# io-board-b-i.net
KiCad netlist of a schematic drawn in EAGLE
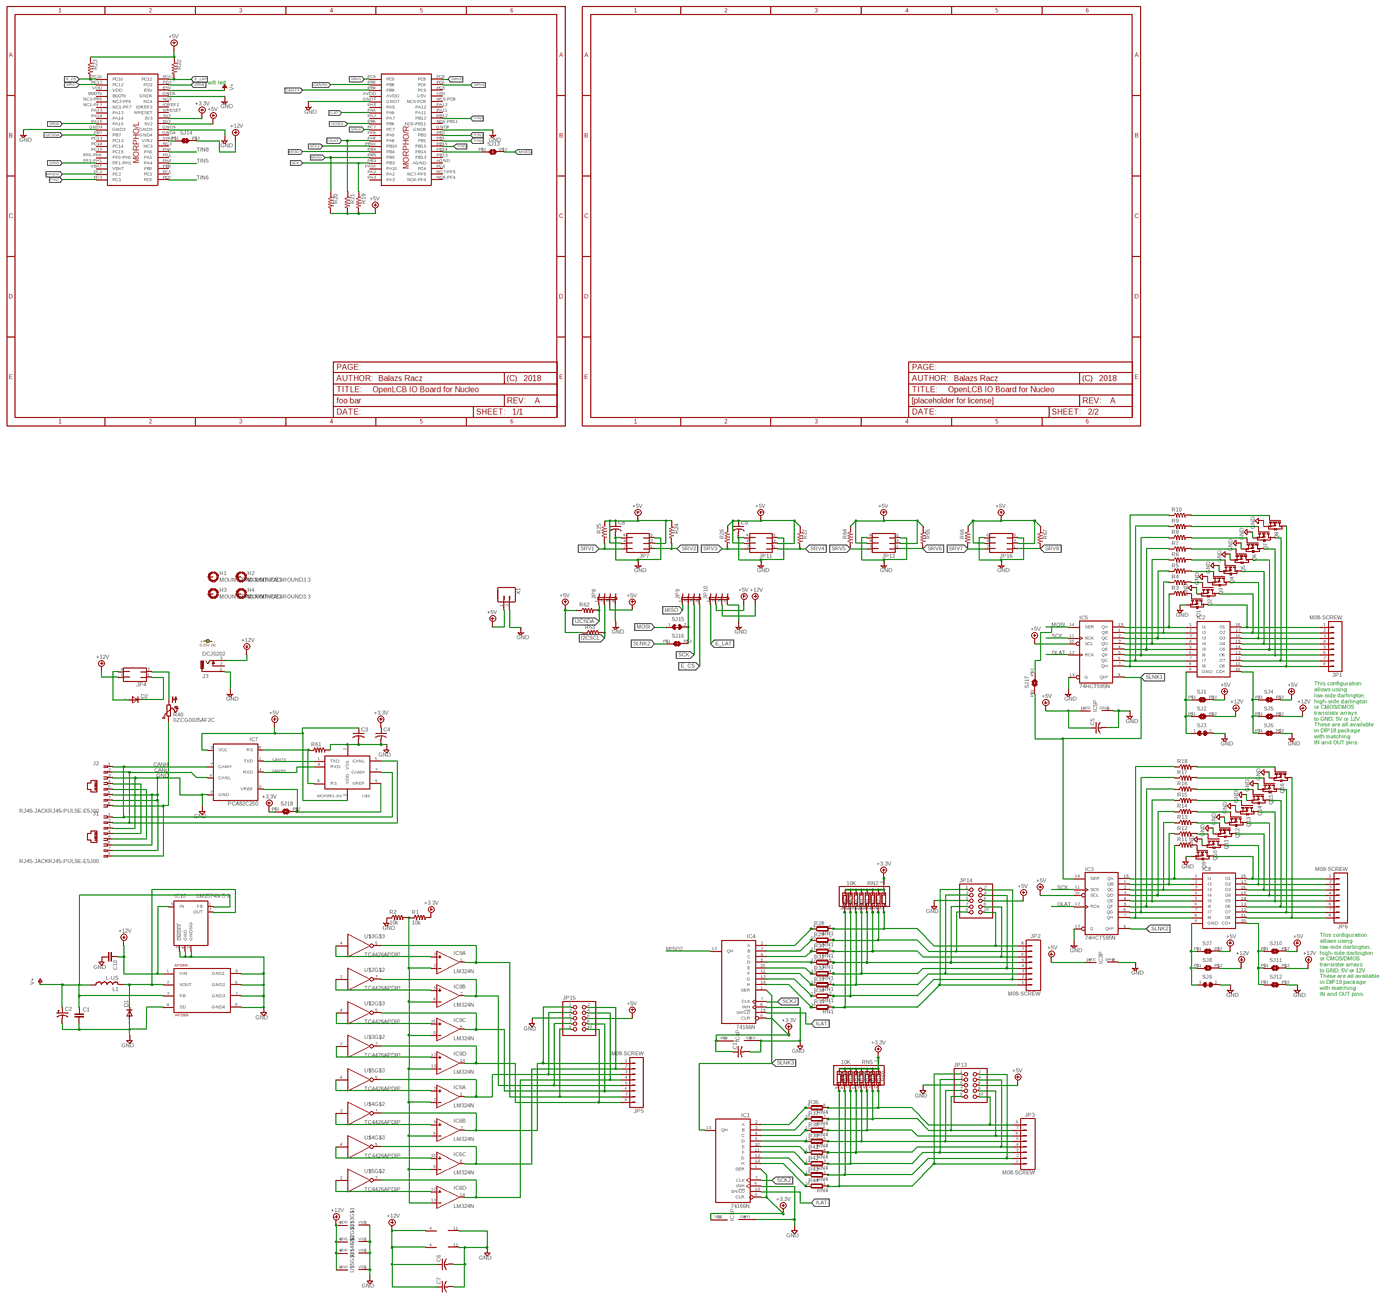
[diagram p0: schematic, sheet 1, overview]
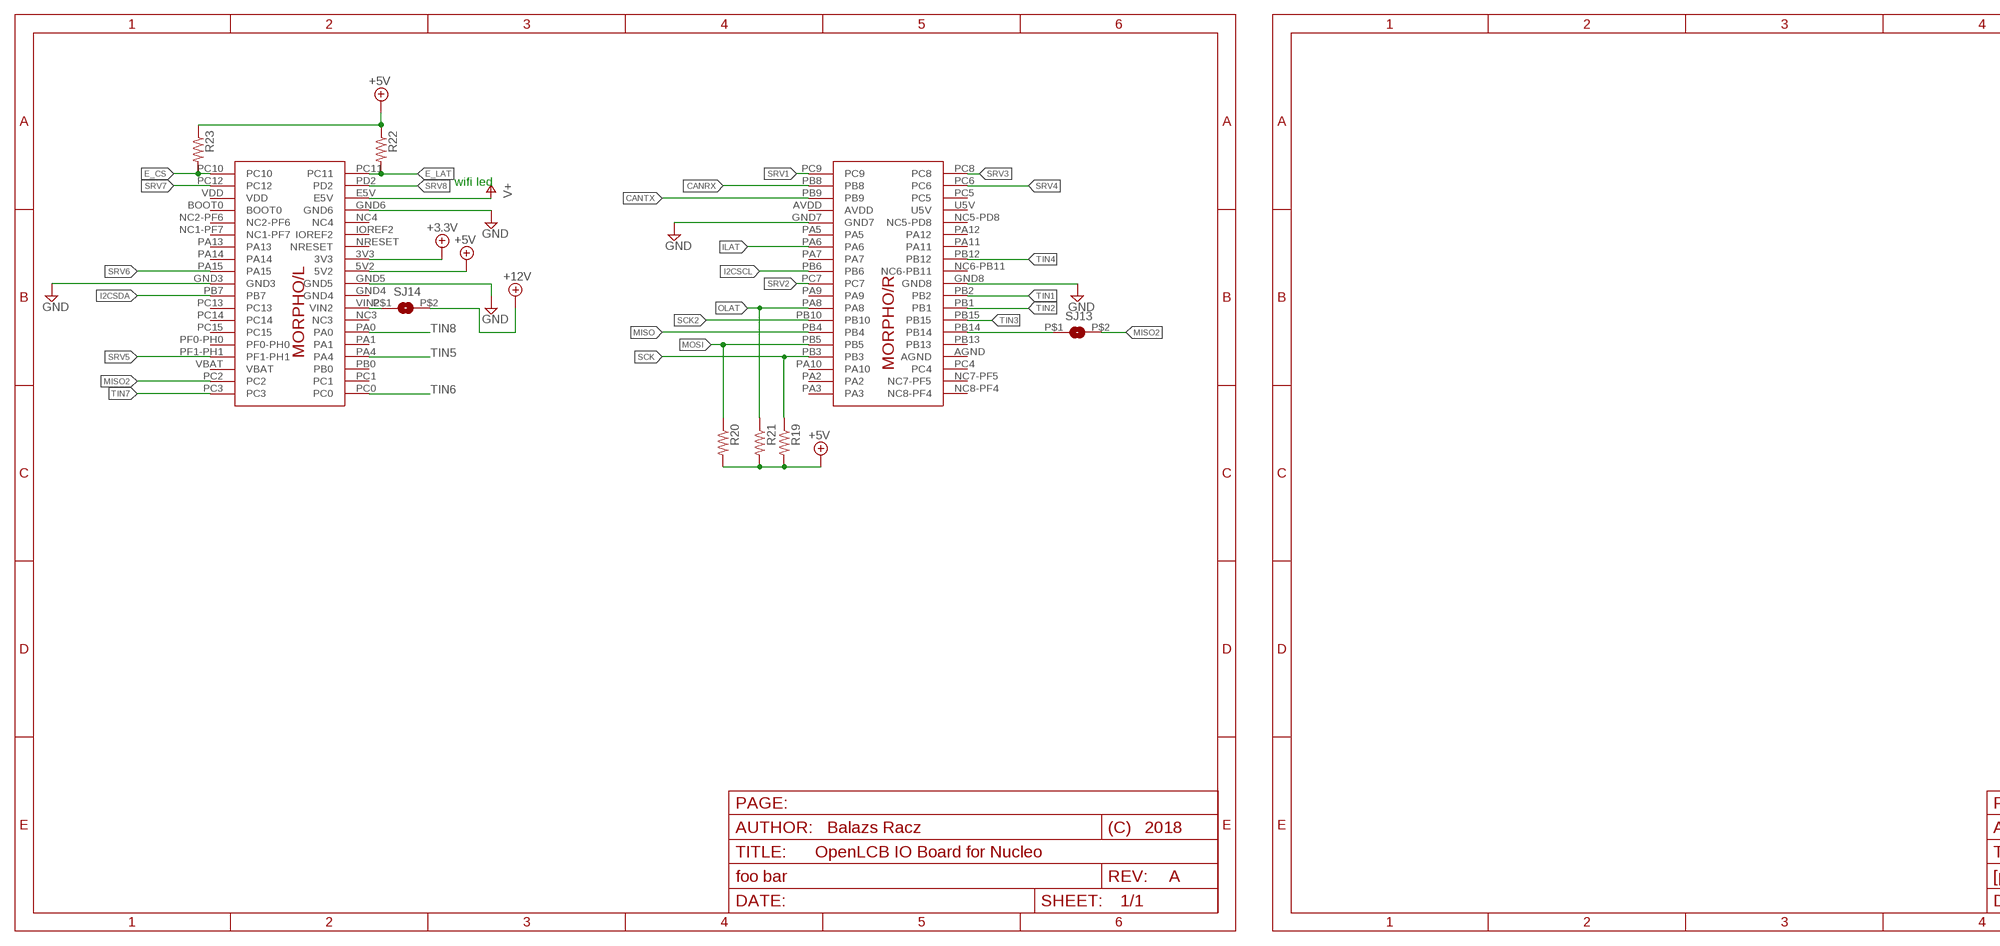
[diagram p1: schematic, sheet 1, part 1 of 4]
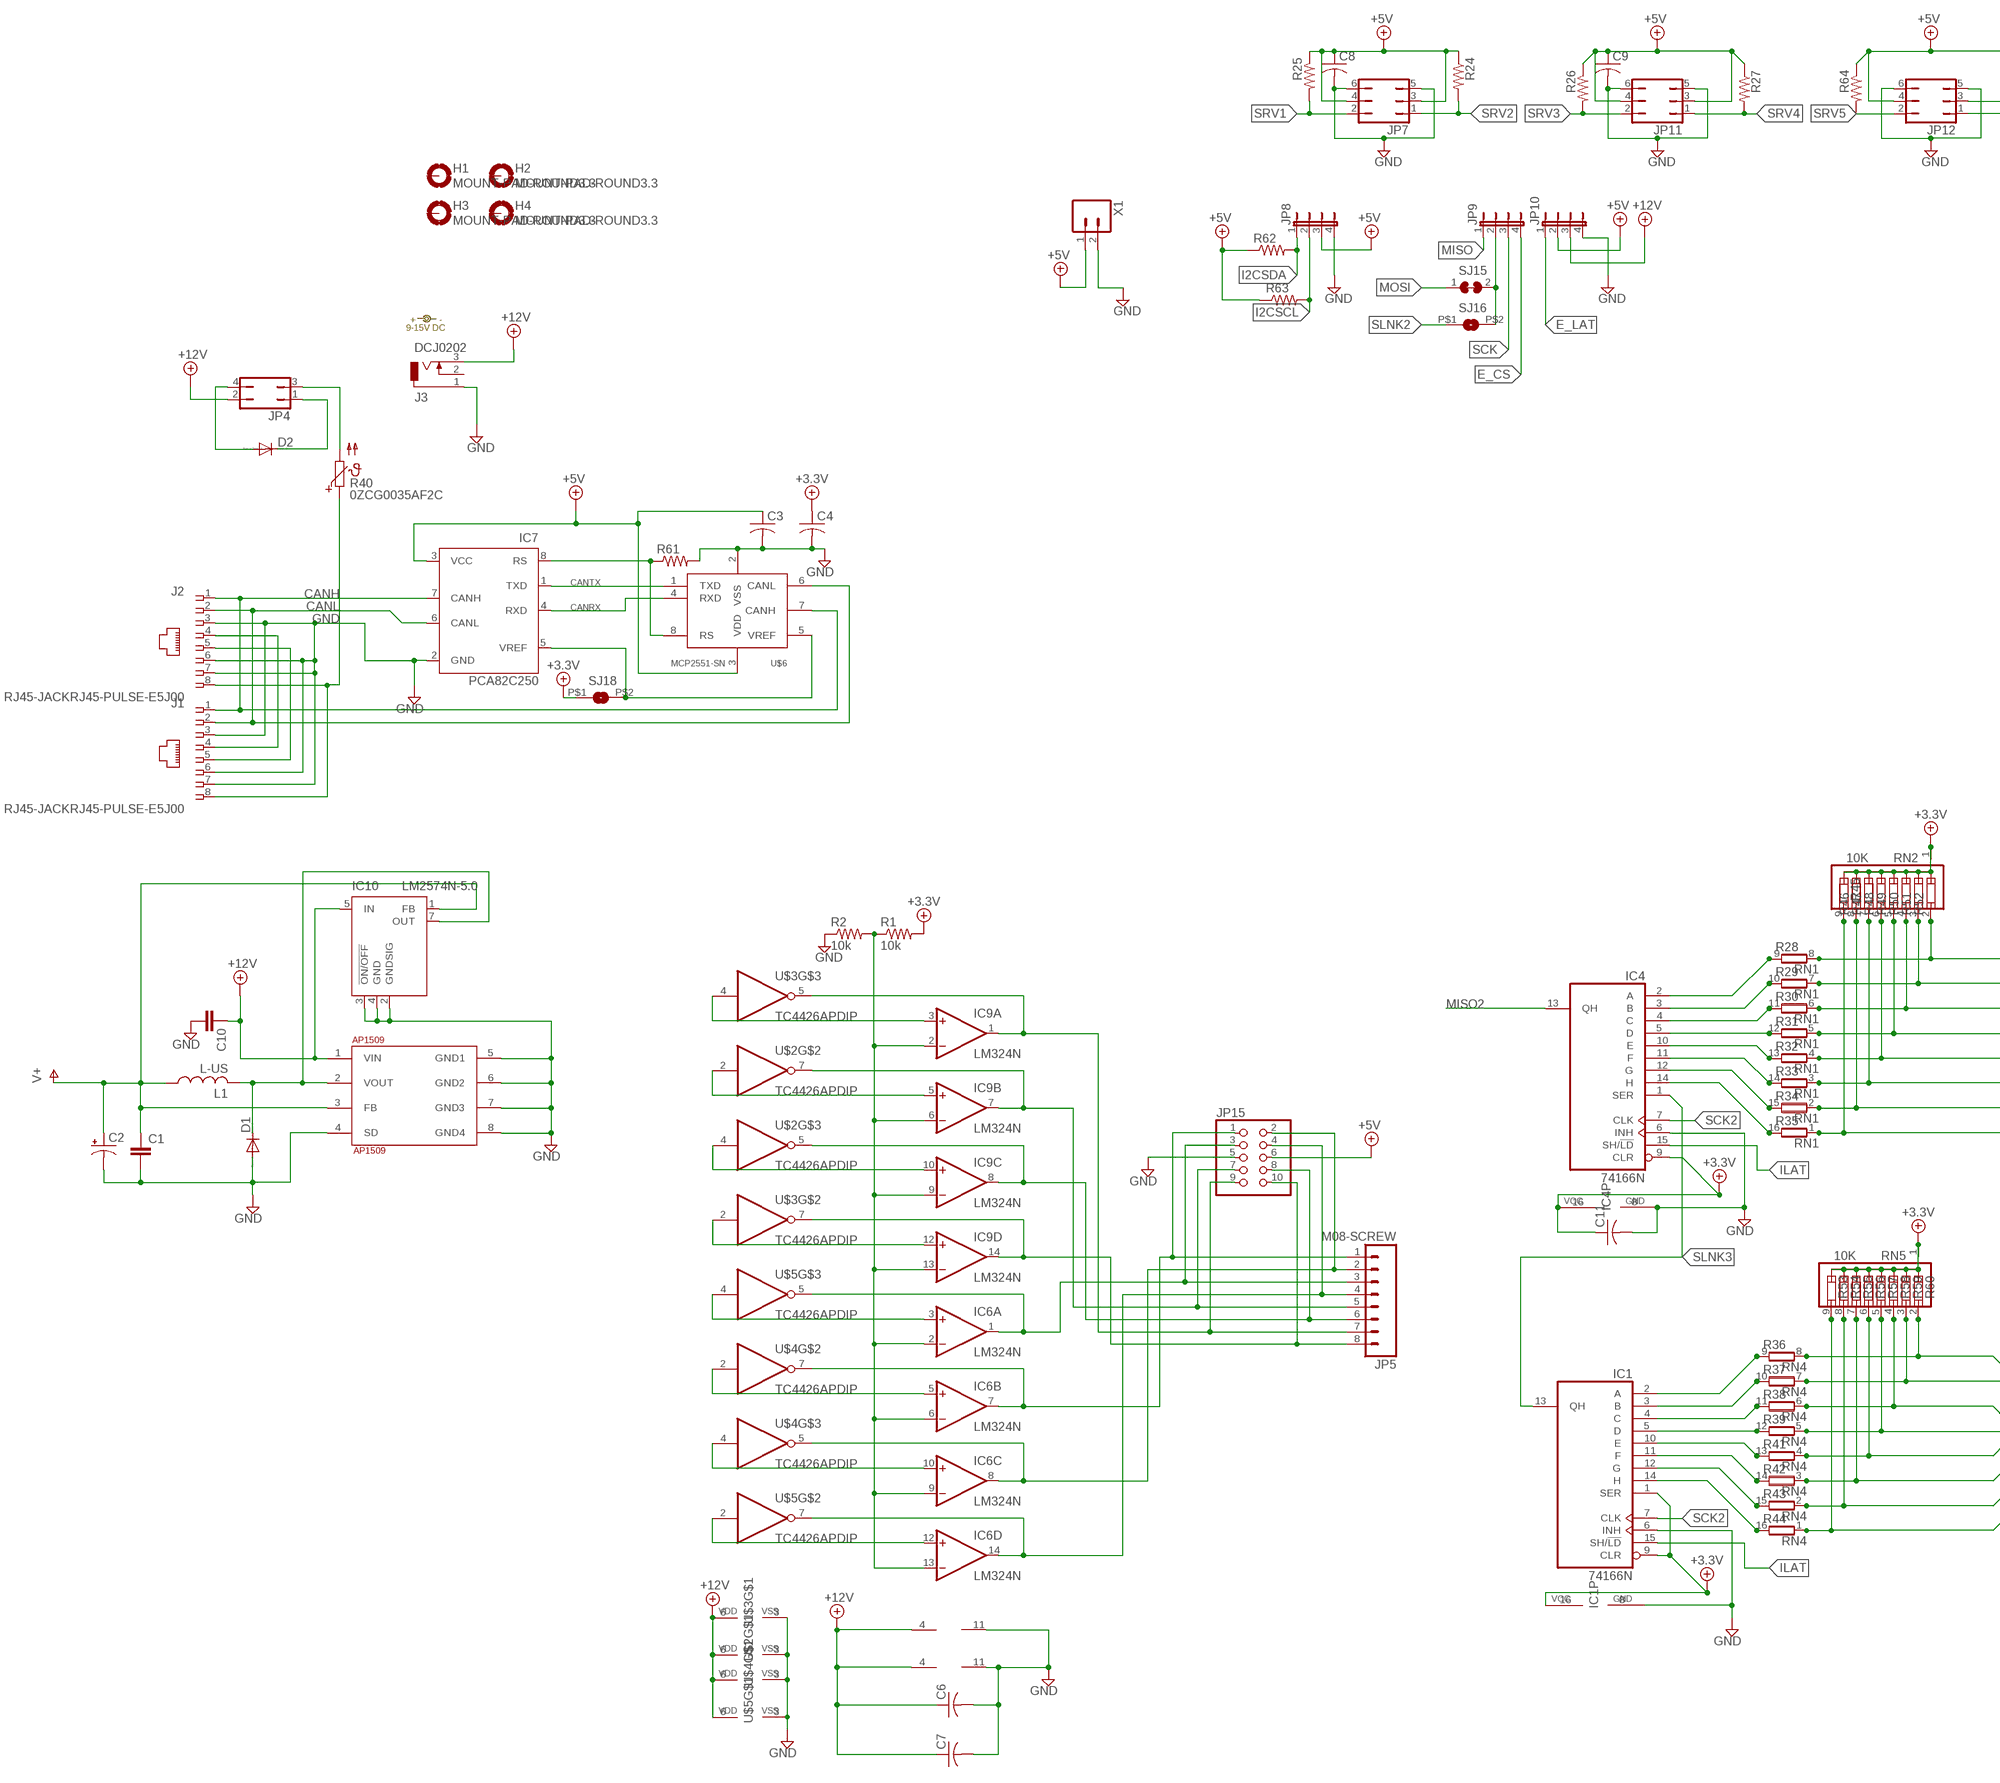
[diagram p2: schematic, sheet 1, part 2 of 4]
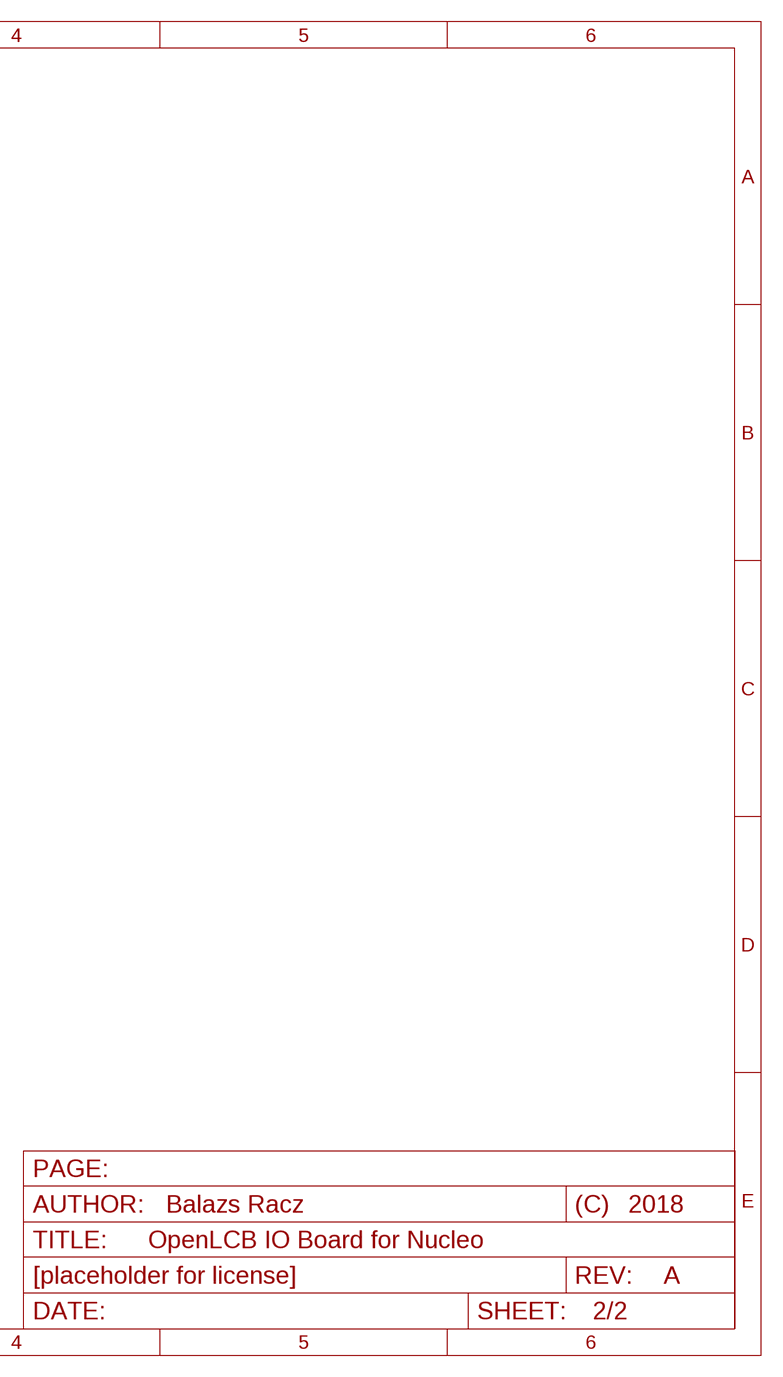
[diagram p3: schematic, sheet 1, part 3 of 4]
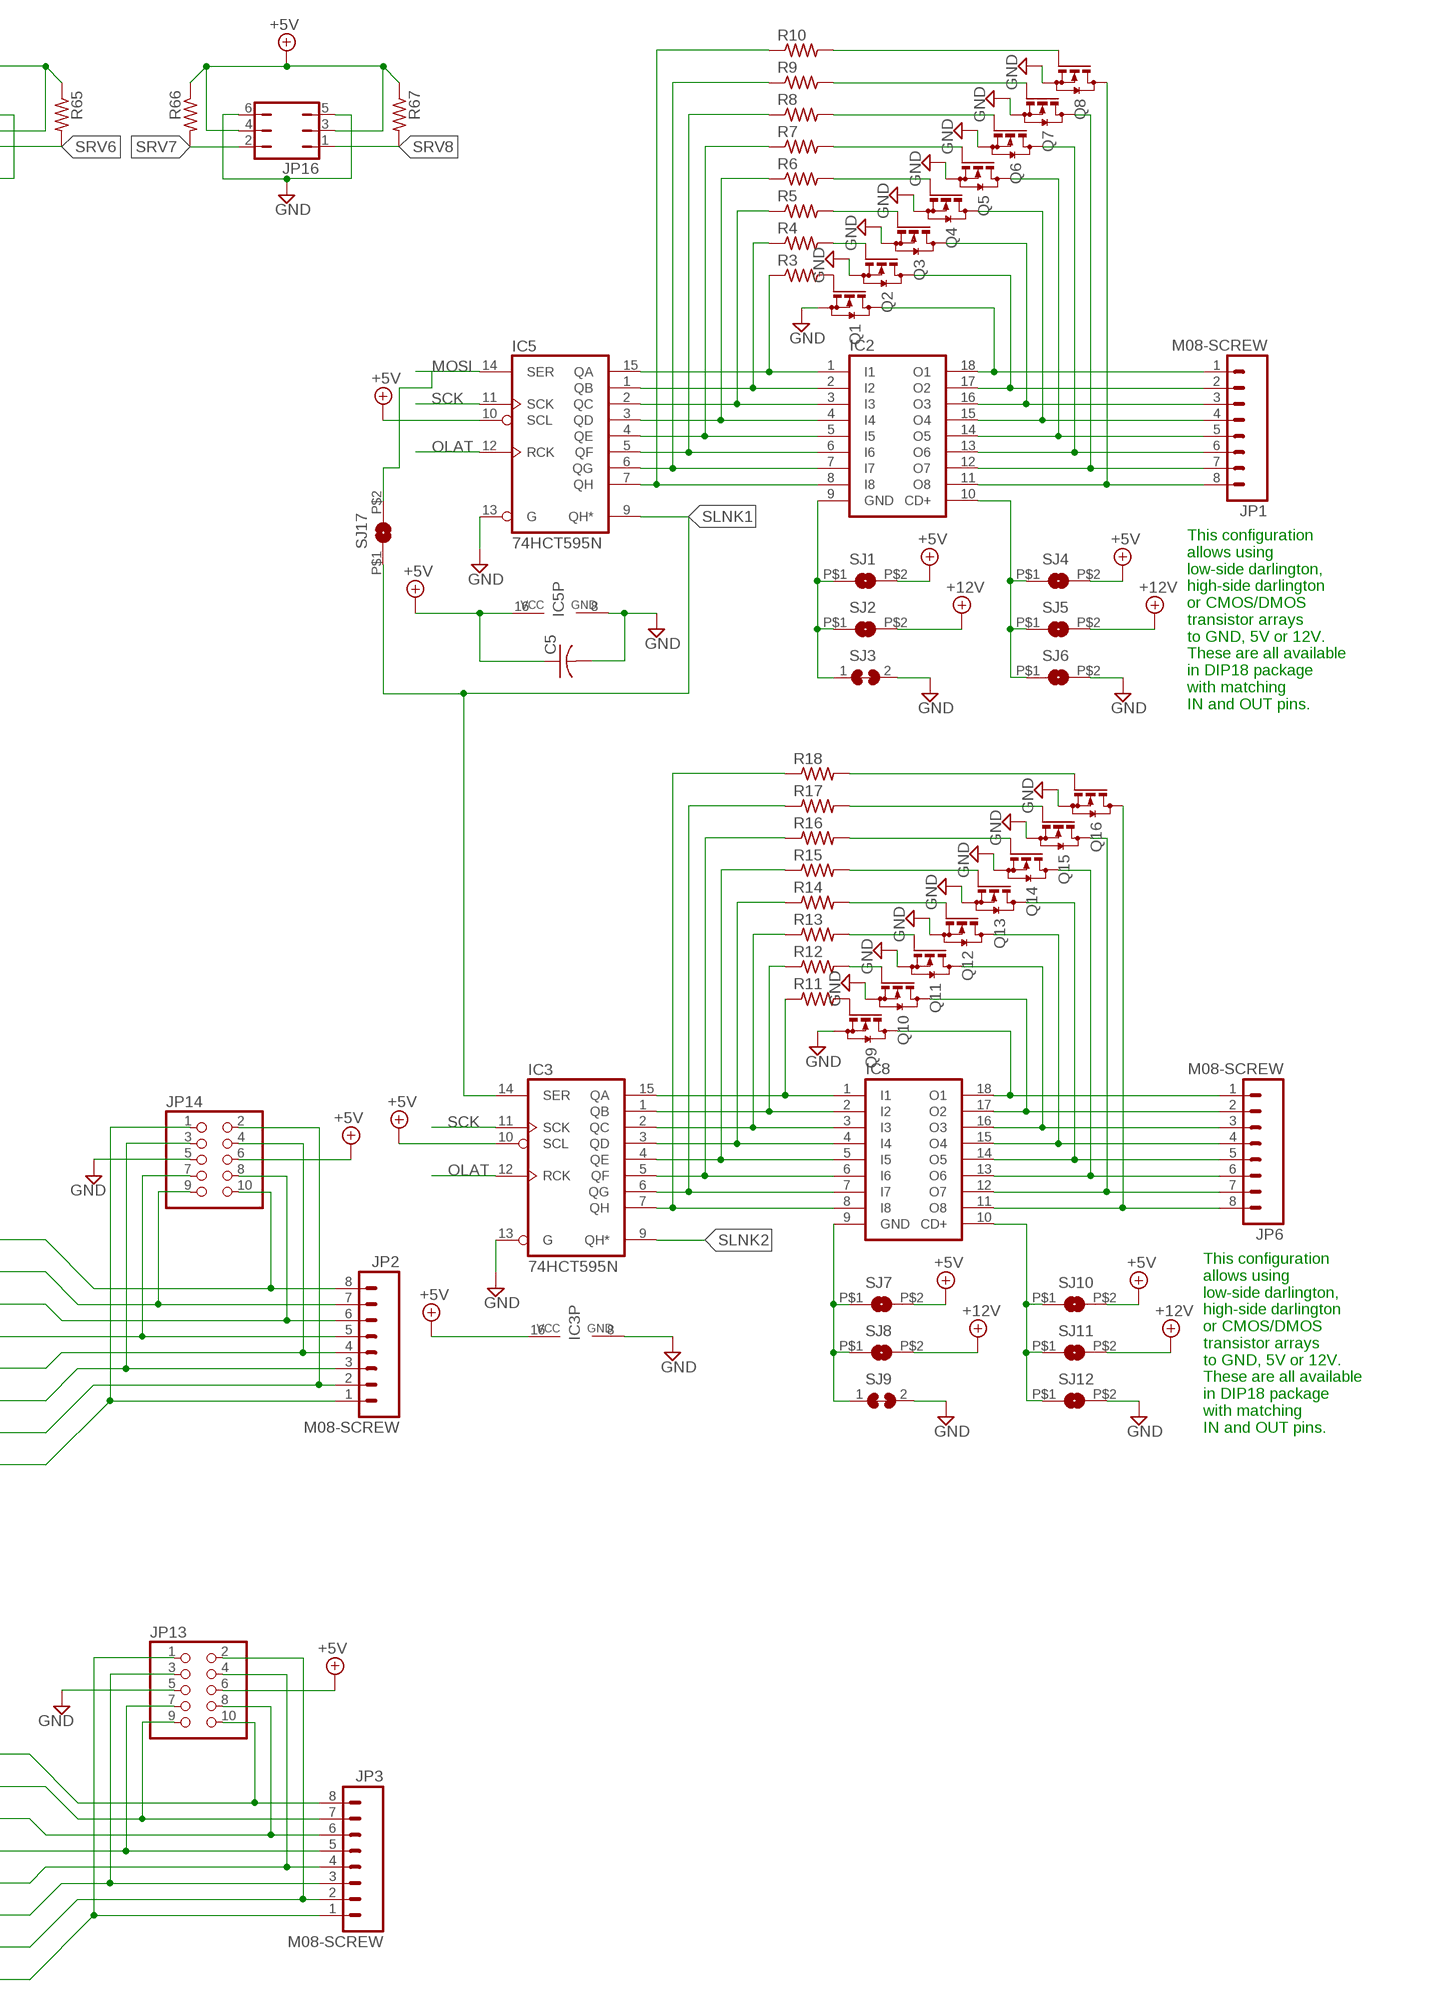
[diagram p4: schematic, sheet 1, part 4 of 4]

(export (version "E")
  (design (tool "Eeschema 10.0.6"))
  (components
    (comp (ref "+12V")
      (value "9-15V DC")
      (footprint "eagle-import:POWER_USAGE")
      (libsource (lib "eagle-import") (part "DOC-POWER_LABEL"))
    )
    (comp (ref "AP1509")
      (value "AP1509")
      (footprint "eagle-import:SO-08")
      (libsource (lib "eagle-import") (part "AP1509"))
    )
    (comp (ref "C1")
      (value "C-EUC1206")
      (footprint "eagle-import:C1206")
      (libsource (lib "eagle-import") (part "C-EUC1206"))
    )
    (comp (ref "C2")
      (value "CPOL-USE2.5-5")
      (footprint "eagle-import:E2,5-5")
      (libsource (lib "eagle-import") (part "CPOL-USE2.5-5"))
    )
    (comp (ref "C3")
      (value "C-USC0805")
      (footprint "eagle-import:C0805")
      (libsource (lib "eagle-import") (part "C-USC0805"))
    )
    (comp (ref "C4")
      (value "C-USC0805")
      (footprint "eagle-import:C0805")
      (libsource (lib "eagle-import") (part "C-USC0805"))
    )
    (comp (ref "C5")
      (value "C-USC0805")
      (footprint "eagle-import:C0805")
      (libsource (lib "eagle-import") (part "C-USC0805"))
    )
    (comp (ref "C6")
      (value "C-USC1206")
      (footprint "eagle-import:C1206")
      (libsource (lib "eagle-import") (part "C-USC1206"))
    )
    (comp (ref "C7")
      (value "C-USC1206")
      (footprint "eagle-import:C1206")
      (libsource (lib "eagle-import") (part "C-USC1206"))
    )
    (comp (ref "C8")
      (value "C-USC1206")
      (footprint "eagle-import:C1206")
      (libsource (lib "eagle-import") (part "C-USC1206"))
    )
    (comp (ref "C9")
      (value "C-USC1206")
      (footprint "eagle-import:C1206")
      (libsource (lib "eagle-import") (part "C-USC1206"))
    )
    (comp (ref "C10")
      (value "C-EUC1206")
      (footprint "eagle-import:C1206")
      (libsource (lib "eagle-import") (part "C-EUC1206"))
    )
    (comp (ref "C11")
      (value "C-USC0805")
      (footprint "eagle-import:C0805")
      (libsource (lib "eagle-import") (part "C-USC0805"))
    )
    (comp (ref "D1")
      (value "DIODE-DO41-7.6")
      (footprint "eagle-import:DO41-7.6")
      (libsource (lib "eagle-import") (part "DIODE-DO41-7.6"))
    )
    (comp (ref "D2")
      (value "DIODE-DO41-7.6")
      (footprint "eagle-import:DO41-7.6")
      (libsource (lib "eagle-import") (part "DIODE-DO41-7.6"))
    )
    (comp (ref "H1")
      (value "MOUNT-PAD-ROUND3.3")
      (footprint "eagle-import:3,3-PAD")
      (libsource (lib "eagle-import") (part "MOUNT-PAD-ROUND3.3"))
    )
    (comp (ref "H2")
      (value "MOUNT-PAD-ROUND3.3")
      (footprint "eagle-import:3,3-PAD")
      (libsource (lib "eagle-import") (part "MOUNT-PAD-ROUND3.3"))
    )
    (comp (ref "H3")
      (value "MOUNT-PAD-ROUND3.3")
      (footprint "eagle-import:3,3-PAD")
      (libsource (lib "eagle-import") (part "MOUNT-PAD-ROUND3.3"))
    )
    (comp (ref "H4")
      (value "MOUNT-PAD-ROUND3.3")
      (footprint "eagle-import:3,3-PAD")
      (libsource (lib "eagle-import") (part "MOUNT-PAD-ROUND3.3"))
    )
    (comp (ref "IC1")
      (value "74166N")
      (footprint "eagle-import:DIL16")
      (libsource (lib "eagle-import") (part "74166N"))
    )
    (comp (ref "IC2")
      (value "ULN2803A")
      (footprint "eagle-import:DIL18-THIN")
      (libsource (lib "eagle-import") (part "ULN2803A"))
    )
    (comp (ref "IC3")
      (value "74HCT595N")
      (footprint "eagle-import:DIL16")
      (libsource (lib "eagle-import") (part "74595NHCT"))
    )
    (comp (ref "IC4")
      (value "74166N")
      (footprint "eagle-import:DIL16")
      (libsource (lib "eagle-import") (part "74166N"))
    )
    (comp (ref "IC5")
      (value "74HCT595N")
      (footprint "eagle-import:DIL16")
      (libsource (lib "eagle-import") (part "74595NHCT"))
    )
    (comp (ref "IC6")
      (value "LM324N")
      (footprint "eagle-import:DIL14")
      (libsource (lib "eagle-import") (part "LM324N"))
    )
    (comp (ref "IC7")
      (value "PCA82C250")
      (footprint "eagle-import:DIL08")
      (libsource (lib "eagle-import") (part "PCA82C250"))
    )
    (comp (ref "IC8")
      (value "ULN2803A")
      (footprint "eagle-import:DIL18-THIN")
      (libsource (lib "eagle-import") (part "ULN2803A"))
    )
    (comp (ref "IC9")
      (value "LM324N")
      (footprint "eagle-import:DIL14")
      (libsource (lib "eagle-import") (part "LM324N"))
    )
    (comp (ref "IC10")
      (value "LM2574N-5.0")
      (footprint "eagle-import:DIL08")
      (libsource (lib "eagle-import") (part "LM2574?-N5.0"))
    )
    (comp (ref "J1")
      (value "RJ45-JACKRJ45-PULSE-E5J00")
      (footprint "eagle-import:RJ45-PULSE-E5J88")
      (libsource (lib "eagle-import") (part "RJ45-JACKRJ45-PULSE-E5J00"))
    )
    (comp (ref "J2")
      (value "RJ45-JACKRJ45-PULSE-E5J00")
      (footprint "eagle-import:RJ45-PULSE-E5J88")
      (libsource (lib "eagle-import") (part "RJ45-JACKRJ45-PULSE-E5J00"))
    )
    (comp (ref "J3")
      (value "DCJ0202")
      (footprint "eagle-import:DCJ0202")
      (libsource (lib "eagle-import") (part "DCJ0202"))
    )
    (comp (ref "JP1")
      (value "M08-SCREW")
      (footprint "eagle-import:1X08_TERMINAL")
      (libsource (lib "eagle-import") (part "M08-SCREW"))
    )
    (comp (ref "JP2")
      (value "M08-SCREW")
      (footprint "eagle-import:1X08_TERMINAL")
      (libsource (lib "eagle-import") (part "M08-SCREW"))
    )
    (comp (ref "JP3")
      (value "M08-SCREW")
      (footprint "eagle-import:1X08_TERMINAL")
      (libsource (lib "eagle-import") (part "M08-SCREW"))
    )
    (comp (ref "JP4")
      (value "JP2Q")
      (footprint "eagle-import:JP2Q")
      (libsource (lib "eagle-import") (part "JP2Q"))
    )
    (comp (ref "JP5")
      (value "M08-SCREW")
      (footprint "eagle-import:1X08_TERMINAL")
      (libsource (lib "eagle-import") (part "M08-SCREW"))
    )
    (comp (ref "JP6")
      (value "M08-SCREW")
      (footprint "eagle-import:1X08_TERMINAL")
      (libsource (lib "eagle-import") (part "M08-SCREW"))
    )
    (comp (ref "JP7")
      (value "JP3Q")
      (footprint "eagle-import:JP3Q")
      (libsource (lib "eagle-import") (part "JP3Q"))
    )
    (comp (ref "JP8")
      (value "JP4-FLAT")
      (footprint "eagle-import:JP4F")
      (libsource (lib "eagle-import") (part "JP4-FLAT"))
    )
    (comp (ref "JP9")
      (value "JP4-FLAT")
      (footprint "eagle-import:JP4F")
      (libsource (lib "eagle-import") (part "JP4-FLAT"))
    )
    (comp (ref "JP10")
      (value "JP4-FLAT")
      (footprint "eagle-import:JP4F")
      (libsource (lib "eagle-import") (part "JP4-FLAT"))
    )
    (comp (ref "JP11")
      (value "JP3Q")
      (footprint "eagle-import:JP3Q")
      (libsource (lib "eagle-import") (part "JP3Q"))
    )
    (comp (ref "JP12")
      (value "JP3Q")
      (footprint "eagle-import:JP3Q")
      (libsource (lib "eagle-import") (part "JP3Q"))
    )
    (comp (ref "JP13")
      (value "PINHD-2X5CN")
      (footprint "eagle-import:CON10M")
      (libsource (lib "eagle-import") (part "PINHD-2X5CN"))
    )
    (comp (ref "JP14")
      (value "PINHD-2X5CN")
      (footprint "eagle-import:CON10M")
      (libsource (lib "eagle-import") (part "PINHD-2X5CN"))
    )
    (comp (ref "JP15")
      (value "PINHD-2X5CN")
      (footprint "eagle-import:CON10M")
      (libsource (lib "eagle-import") (part "PINHD-2X5CN"))
    )
    (comp (ref "JP16")
      (value "JP3Q")
      (footprint "eagle-import:JP3Q")
      (libsource (lib "eagle-import") (part "JP3Q"))
    )
    (comp (ref "L1")
      (value "L-US")
      (footprint "eagle-import:L5-8,5")
      (libsource (lib "eagle-import") (part "L-US"))
    )
    (comp (ref "Q1")
      (value "BSS123")
      (footprint "eagle-import:SOT23")
      (libsource (lib "eagle-import") (part "BSS123"))
    )
    (comp (ref "Q2")
      (value "BSS123")
      (footprint "eagle-import:SOT23")
      (libsource (lib "eagle-import") (part "BSS123"))
    )
    (comp (ref "Q3")
      (value "BSS123")
      (footprint "eagle-import:SOT23")
      (libsource (lib "eagle-import") (part "BSS123"))
    )
    (comp (ref "Q4")
      (value "BSS123")
      (footprint "eagle-import:SOT23")
      (libsource (lib "eagle-import") (part "BSS123"))
    )
    (comp (ref "Q5")
      (value "BSS123")
      (footprint "eagle-import:SOT23")
      (libsource (lib "eagle-import") (part "BSS123"))
    )
    (comp (ref "Q6")
      (value "BSS123")
      (footprint "eagle-import:SOT23")
      (libsource (lib "eagle-import") (part "BSS123"))
    )
    (comp (ref "Q7")
      (value "BSS123")
      (footprint "eagle-import:SOT23")
      (libsource (lib "eagle-import") (part "BSS123"))
    )
    (comp (ref "Q8")
      (value "BSS123")
      (footprint "eagle-import:SOT23")
      (libsource (lib "eagle-import") (part "BSS123"))
    )
    (comp (ref "Q9")
      (value "BSS123")
      (footprint "eagle-import:SOT23")
      (libsource (lib "eagle-import") (part "BSS123"))
    )
    (comp (ref "Q10")
      (value "BSS123")
      (footprint "eagle-import:SOT23")
      (libsource (lib "eagle-import") (part "BSS123"))
    )
    (comp (ref "Q11")
      (value "BSS123")
      (footprint "eagle-import:SOT23")
      (libsource (lib "eagle-import") (part "BSS123"))
    )
    (comp (ref "Q12")
      (value "BSS123")
      (footprint "eagle-import:SOT23")
      (libsource (lib "eagle-import") (part "BSS123"))
    )
    (comp (ref "Q13")
      (value "BSS123")
      (footprint "eagle-import:SOT23")
      (libsource (lib "eagle-import") (part "BSS123"))
    )
    (comp (ref "Q14")
      (value "BSS123")
      (footprint "eagle-import:SOT23")
      (libsource (lib "eagle-import") (part "BSS123"))
    )
    (comp (ref "Q15")
      (value "BSS123")
      (footprint "eagle-import:SOT23")
      (libsource (lib "eagle-import") (part "BSS123"))
    )
    (comp (ref "Q16")
      (value "BSS123")
      (footprint "eagle-import:SOT23")
      (libsource (lib "eagle-import") (part "BSS123"))
    )
    (comp (ref "R1")
      (value "10k")
      (footprint "eagle-import:R0805")
      (libsource (lib "eagle-import") (part "R-US_R0805"))
    )
    (comp (ref "R2")
      (value "10k")
      (footprint "eagle-import:R0805")
      (libsource (lib "eagle-import") (part "R-US_R0805"))
    )
    (comp (ref "R3")
      (value "R-US_R0603")
      (footprint "eagle-import:R0603")
      (libsource (lib "eagle-import") (part "R-US_R0603"))
    )
    (comp (ref "R4")
      (value "R-US_R0603")
      (footprint "eagle-import:R0603")
      (libsource (lib "eagle-import") (part "R-US_R0603"))
    )
    (comp (ref "R5")
      (value "R-US_R0603")
      (footprint "eagle-import:R0603")
      (libsource (lib "eagle-import") (part "R-US_R0603"))
    )
    (comp (ref "R6")
      (value "R-US_R0603")
      (footprint "eagle-import:R0603")
      (libsource (lib "eagle-import") (part "R-US_R0603"))
    )
    (comp (ref "R7")
      (value "R-US_R0603")
      (footprint "eagle-import:R0603")
      (libsource (lib "eagle-import") (part "R-US_R0603"))
    )
    (comp (ref "R8")
      (value "R-US_R0603")
      (footprint "eagle-import:R0603")
      (libsource (lib "eagle-import") (part "R-US_R0603"))
    )
    (comp (ref "R9")
      (value "R-US_R0603")
      (footprint "eagle-import:R0603")
      (libsource (lib "eagle-import") (part "R-US_R0603"))
    )
    (comp (ref "R10")
      (value "R-US_R0603")
      (footprint "eagle-import:R0603")
      (libsource (lib "eagle-import") (part "R-US_R0603"))
    )
    (comp (ref "R11")
      (value "R-US_R0603")
      (footprint "eagle-import:R0603")
      (libsource (lib "eagle-import") (part "R-US_R0603"))
    )
    (comp (ref "R12")
      (value "R-US_R0603")
      (footprint "eagle-import:R0603")
      (libsource (lib "eagle-import") (part "R-US_R0603"))
    )
    (comp (ref "R13")
      (value "R-US_R0603")
      (footprint "eagle-import:R0603")
      (libsource (lib "eagle-import") (part "R-US_R0603"))
    )
    (comp (ref "R14")
      (value "R-US_R0603")
      (footprint "eagle-import:R0603")
      (libsource (lib "eagle-import") (part "R-US_R0603"))
    )
    (comp (ref "R15")
      (value "R-US_R0603")
      (footprint "eagle-import:R0603")
      (libsource (lib "eagle-import") (part "R-US_R0603"))
    )
    (comp (ref "R16")
      (value "R-US_R0603")
      (footprint "eagle-import:R0603")
      (libsource (lib "eagle-import") (part "R-US_R0603"))
    )
    (comp (ref "R17")
      (value "R-US_R0603")
      (footprint "eagle-import:R0603")
      (libsource (lib "eagle-import") (part "R-US_R0603"))
    )
    (comp (ref "R18")
      (value "R-US_R0603")
      (footprint "eagle-import:R0603")
      (libsource (lib "eagle-import") (part "R-US_R0603"))
    )
    (comp (ref "R19")
      (value "R-US_R0805")
      (footprint "eagle-import:R0805")
      (libsource (lib "eagle-import") (part "rcl_334_R-US_R0805"))
    )
    (comp (ref "R20")
      (value "R-US_R0805")
      (footprint "eagle-import:R0805")
      (libsource (lib "eagle-import") (part "rcl_334_R-US_R0805"))
    )
    (comp (ref "R21")
      (value "R-US_R0805")
      (footprint "eagle-import:R0805")
      (libsource (lib "eagle-import") (part "rcl_334_R-US_R0805"))
    )
    (comp (ref "R22")
      (value "R-US_R0805")
      (footprint "eagle-import:R0805")
      (libsource (lib "eagle-import") (part "rcl_334_R-US_R0805"))
    )
    (comp (ref "R23")
      (value "R-US_R0805")
      (footprint "eagle-import:R0805")
      (libsource (lib "eagle-import") (part "rcl_334_R-US_R0805"))
    )
    (comp (ref "R24")
      (value "R-US_R0805")
      (footprint "eagle-import:R0805")
      (libsource (lib "eagle-import") (part "rcl_334_R-US_R0805"))
    )
    (comp (ref "R25")
      (value "R-US_R0805")
      (footprint "eagle-import:R0805")
      (libsource (lib "eagle-import") (part "rcl_334_R-US_R0805"))
    )
    (comp (ref "R26")
      (value "R-US_R0805")
      (footprint "eagle-import:R0805")
      (libsource (lib "eagle-import") (part "rcl_334_R-US_R0805"))
    )
    (comp (ref "R27")
      (value "R-US_R0805")
      (footprint "eagle-import:R0805")
      (libsource (lib "eagle-import") (part "rcl_334_R-US_R0805"))
    )
    (comp (ref "R28")
      (value "R-EU_R0603")
      (footprint "eagle-import:R0603")
      (libsource (lib "eagle-import") (part "R-EU_R0603"))
    )
    (comp (ref "R29")
      (value "R-EU_R0603")
      (footprint "eagle-import:R0603")
      (libsource (lib "eagle-import") (part "R-EU_R0603"))
    )
    (comp (ref "R30")
      (value "R-EU_R0603")
      (footprint "eagle-import:R0603")
      (libsource (lib "eagle-import") (part "R-EU_R0603"))
    )
    (comp (ref "R31")
      (value "R-EU_R0603")
      (footprint "eagle-import:R0603")
      (libsource (lib "eagle-import") (part "R-EU_R0603"))
    )
    (comp (ref "R32")
      (value "R-EU_R0603")
      (footprint "eagle-import:R0603")
      (libsource (lib "eagle-import") (part "R-EU_R0603"))
    )
    (comp (ref "R33")
      (value "R-EU_R0603")
      (footprint "eagle-import:R0603")
      (libsource (lib "eagle-import") (part "R-EU_R0603"))
    )
    (comp (ref "R34")
      (value "R-EU_R0603")
      (footprint "eagle-import:R0603")
      (libsource (lib "eagle-import") (part "R-EU_R0603"))
    )
    (comp (ref "R35")
      (value "R-EU_R0603")
      (footprint "eagle-import:R0603")
      (libsource (lib "eagle-import") (part "R-EU_R0603"))
    )
    (comp (ref "R36")
      (value "R-EU_R0603")
      (footprint "eagle-import:R0603")
      (libsource (lib "eagle-import") (part "R-EU_R0603"))
    )
    (comp (ref "R37")
      (value "R-EU_R0603")
      (footprint "eagle-import:R0603")
      (libsource (lib "eagle-import") (part "R-EU_R0603"))
    )
    (comp (ref "R38")
      (value "R-EU_R0603")
      (footprint "eagle-import:R0603")
      (libsource (lib "eagle-import") (part "R-EU_R0603"))
    )
    (comp (ref "R39")
      (value "R-EU_R0603")
      (footprint "eagle-import:R0603")
      (libsource (lib "eagle-import") (part "R-EU_R0603"))
    )
    (comp (ref "R40")
      (value "0ZCG0035AF2C")
      (footprint "eagle-import:PTC1812")
      (libsource (lib "eagle-import") (part "PTC_1812"))
    )
    (comp (ref "R41")
      (value "R-EU_R0603")
      (footprint "eagle-import:R0603")
      (libsource (lib "eagle-import") (part "R-EU_R0603"))
    )
    (comp (ref "R42")
      (value "R-EU_R0603")
      (footprint "eagle-import:R0603")
      (libsource (lib "eagle-import") (part "R-EU_R0603"))
    )
    (comp (ref "R43")
      (value "R-EU_R0603")
      (footprint "eagle-import:R0603")
      (libsource (lib "eagle-import") (part "R-EU_R0603"))
    )
    (comp (ref "R44")
      (value "R-EU_R0603")
      (footprint "eagle-import:R0603")
      (libsource (lib "eagle-import") (part "R-EU_R0603"))
    )
    (comp (ref "R45")
      (value "R-EU_R0603")
      (footprint "eagle-import:R0603")
      (libsource (lib "eagle-import") (part "R-EU_R0603"))
    )
    (comp (ref "R46")
      (value "R-EU_R0603")
      (footprint "eagle-import:R0603")
      (libsource (lib "eagle-import") (part "R-EU_R0603"))
    )
    (comp (ref "R47")
      (value "R-EU_R0603")
      (footprint "eagle-import:R0603")
      (libsource (lib "eagle-import") (part "R-EU_R0603"))
    )
    (comp (ref "R48")
      (value "R-EU_R0603")
      (footprint "eagle-import:R0603")
      (libsource (lib "eagle-import") (part "R-EU_R0603"))
    )
    (comp (ref "R49")
      (value "R-EU_R0603")
      (footprint "eagle-import:R0603")
      (libsource (lib "eagle-import") (part "R-EU_R0603"))
    )
    (comp (ref "R50")
      (value "R-EU_R0603")
      (footprint "eagle-import:R0603")
      (libsource (lib "eagle-import") (part "R-EU_R0603"))
    )
    (comp (ref "R51")
      (value "R-EU_R0603")
      (footprint "eagle-import:R0603")
      (libsource (lib "eagle-import") (part "R-EU_R0603"))
    )
    (comp (ref "R52")
      (value "R-EU_R0603")
      (footprint "eagle-import:R0603")
      (libsource (lib "eagle-import") (part "R-EU_R0603"))
    )
    (comp (ref "R53")
      (value "R-EU_R0603")
      (footprint "eagle-import:R0603")
      (libsource (lib "eagle-import") (part "R-EU_R0603"))
    )
    (comp (ref "R54")
      (value "R-EU_R0603")
      (footprint "eagle-import:R0603")
      (libsource (lib "eagle-import") (part "R-EU_R0603"))
    )
    (comp (ref "R55")
      (value "R-EU_R0603")
      (footprint "eagle-import:R0603")
      (libsource (lib "eagle-import") (part "R-EU_R0603"))
    )
    (comp (ref "R56")
      (value "R-EU_R0603")
      (footprint "eagle-import:R0603")
      (libsource (lib "eagle-import") (part "R-EU_R0603"))
    )
    (comp (ref "R57")
      (value "R-EU_R0603")
      (footprint "eagle-import:R0603")
      (libsource (lib "eagle-import") (part "R-EU_R0603"))
    )
    (comp (ref "R58")
      (value "R-EU_R0603")
      (footprint "eagle-import:R0603")
      (libsource (lib "eagle-import") (part "R-EU_R0603"))
    )
    (comp (ref "R59")
      (value "R-EU_R0603")
      (footprint "eagle-import:R0603")
      (libsource (lib "eagle-import") (part "R-EU_R0603"))
    )
    (comp (ref "R60")
      (value "R-EU_R0603")
      (footprint "eagle-import:R0603")
      (libsource (lib "eagle-import") (part "R-EU_R0603"))
    )
    (comp (ref "R61")
      (value "R-US_R0805")
      (footprint "eagle-import:R0805")
      (libsource (lib "eagle-import") (part "rcl_334_R-US_R0805"))
    )
    (comp (ref "R62")
      (value "R-US_R0805")
      (footprint "eagle-import:R0805")
      (libsource (lib "eagle-import") (part "rcl_334_R-US_R0805"))
    )
    (comp (ref "R63")
      (value "R-US_R0805")
      (footprint "eagle-import:R0805")
      (libsource (lib "eagle-import") (part "rcl_334_R-US_R0805"))
    )
    (comp (ref "R64")
      (value "R-US_R0805")
      (footprint "eagle-import:R0805")
      (libsource (lib "eagle-import") (part "rcl_334_R-US_R0805"))
    )
    (comp (ref "R65")
      (value "R-US_R0805")
      (footprint "eagle-import:R0805")
      (libsource (lib "eagle-import") (part "rcl_334_R-US_R0805"))
    )
    (comp (ref "R66")
      (value "R-US_R0805")
      (footprint "eagle-import:R0805")
      (libsource (lib "eagle-import") (part "rcl_334_R-US_R0805"))
    )
    (comp (ref "R67")
      (value "R-US_R0805")
      (footprint "eagle-import:R0805")
      (libsource (lib "eagle-import") (part "rcl_334_R-US_R0805"))
    )
    (comp (ref "RN1")
      (value "8R-P")
      (footprint "eagle-import:DIL16")
      (libsource (lib "eagle-import") (part "8R-P"))
    )
    (comp (ref "RN2")
      (value "10K")
      (footprint "eagle-import:SIL9")
      (libsource (lib "eagle-import") (part "G08R"))
    )
    (comp (ref "RN4")
      (value "8R-P")
      (footprint "eagle-import:DIL16")
      (libsource (lib "eagle-import") (part "8R-P"))
    )
    (comp (ref "RN5")
      (value "10K")
      (footprint "eagle-import:SIL9")
      (libsource (lib "eagle-import") (part "G08R"))
    )
    (comp (ref "SJ1")
      (value "SJRND2")
      (footprint "eagle-import:SJ_RND2")
      (libsource (lib "eagle-import") (part "SJRND2"))
    )
    (comp (ref "SJ2")
      (value "SJRND2")
      (footprint "eagle-import:SJ_RND2")
      (libsource (lib "eagle-import") (part "SJRND2"))
    )
    (comp (ref "SJ3")
      (value "SJ-C")
      (footprint "eagle-import:SJW-C")
      (libsource (lib "eagle-import") (part "SJ-C"))
    )
    (comp (ref "SJ4")
      (value "SJRND2")
      (footprint "eagle-import:SJ_RND2")
      (libsource (lib "eagle-import") (part "SJRND2"))
    )
    (comp (ref "SJ5")
      (value "SJRND2")
      (footprint "eagle-import:SJ_RND2")
      (libsource (lib "eagle-import") (part "SJRND2"))
    )
    (comp (ref "SJ6")
      (value "SJRND2")
      (footprint "eagle-import:SJ_RND2")
      (libsource (lib "eagle-import") (part "SJRND2"))
    )
    (comp (ref "SJ7")
      (value "SJRND2")
      (footprint "eagle-import:SJ_RND2")
      (libsource (lib "eagle-import") (part "SJRND2"))
    )
    (comp (ref "SJ8")
      (value "SJRND2")
      (footprint "eagle-import:SJ_RND2")
      (libsource (lib "eagle-import") (part "SJRND2"))
    )
    (comp (ref "SJ9")
      (value "SJ-C")
      (footprint "eagle-import:SJW-C")
      (libsource (lib "eagle-import") (part "SJ-C"))
    )
    (comp (ref "SJ10")
      (value "SJRND2")
      (footprint "eagle-import:SJ_RND2")
      (libsource (lib "eagle-import") (part "SJRND2"))
    )
    (comp (ref "SJ11")
      (value "SJRND2")
      (footprint "eagle-import:SJ_RND2")
      (libsource (lib "eagle-import") (part "SJRND2"))
    )
    (comp (ref "SJ12")
      (value "SJRND2")
      (footprint "eagle-import:SJ_RND2")
      (libsource (lib "eagle-import") (part "SJRND2"))
    )
    (comp (ref "SJ13")
      (value "SJRND2")
      (footprint "eagle-import:SJ_RND2")
      (libsource (lib "eagle-import") (part "SJRND2"))
    )
    (comp (ref "SJ14")
      (value "SJRND2")
      (footprint "eagle-import:SJ_RND2")
      (libsource (lib "eagle-import") (part "SJRND2"))
    )
    (comp (ref "SJ15")
      (value "SJ-C")
      (footprint "eagle-import:SJW-C")
      (libsource (lib "eagle-import") (part "SJ-C"))
    )
    (comp (ref "SJ16")
      (value "SJRND2")
      (footprint "eagle-import:SJ_RND2")
      (libsource (lib "eagle-import") (part "SJRND2"))
    )
    (comp (ref "SJ17")
      (value "SJRND2")
      (footprint "eagle-import:SJ_RND2")
      (libsource (lib "eagle-import") (part "SJRND2"))
    )
    (comp (ref "SJ18")
      (value "SJRND2")
      (footprint "eagle-import:SJ_RND2")
      (libsource (lib "eagle-import") (part "SJRND2"))
    )
    (comp (ref "U$1")
      (value "NUCLEO_64_GENERIC")
      (footprint "eagle-import:NUCLEO_BRD_BASE64")
      (libsource (lib "eagle-import") (part "NUCLEO_64_GENERIC"))
    )
    (comp (ref "U$2")
      (value "TC4426APDIP")
      (footprint "eagle-import:DIL08-LONG")
      (libsource (lib "eagle-import") (part "TC4426APDIP"))
    )
    (comp (ref "U$3")
      (value "TC4426APDIP")
      (footprint "eagle-import:DIL08-LONG")
      (libsource (lib "eagle-import") (part "TC4426APDIP"))
    )
    (comp (ref "U$4")
      (value "TC4426APDIP")
      (footprint "eagle-import:DIL08-LONG")
      (libsource (lib "eagle-import") (part "TC4426APDIP"))
    )
    (comp (ref "U$5")
      (value "TC4426APDIP")
      (footprint "eagle-import:DIL08-LONG")
      (libsource (lib "eagle-import") (part "TC4426APDIP"))
    )
    (comp (ref "U$6")
      (value "MCP2551-SN")
      (footprint "eagle-import:SO-08")
      (libsource (lib "eagle-import") (part "MCP2551-SN"))
    )
    (comp (ref "X1")
      (value "CONNECTOR-M023.5MM-LOCK")
      (footprint "eagle-import:SCREWTERMINAL-3.5MM-2_LOCK")
      (libsource (lib "eagle-import") (part "CONNECTOR-M023.5MM-LOCK"))
    )
  )
  (nets
    (net (code "1") (name "+3.3V") (class "Default")
      (node (ref "C11") (pin "1") (pinfunction "1_1") (pintype "passive"))
      (node (ref "C4") (pin "1") (pinfunction "1_1") (pintype "passive"))
      (node (ref "IC1") (pin "1") (pinfunction "SER_1") (pintype "input"))
      (node (ref "IC1") (pin "16") (pinfunction "VCC_16") (pintype "power_in"))
      (node (ref "IC1") (pin "9") (pinfunction "CLR_9") (pintype "input"))
      (node (ref "IC4") (pin "16") (pinfunction "VCC_16") (pintype "power_in"))
      (node (ref "IC4") (pin "9") (pinfunction "CLR_9") (pintype "input"))
      (node (ref "R1") (pin "2") (pinfunction "2_2") (pintype "passive"))
      (node (ref "R45") (pin "1") (pinfunction "1_1") (pintype "passive"))
      (node (ref "R46") (pin "2") (pinfunction "2_2") (pintype "passive"))
      (node (ref "R47") (pin "2") (pinfunction "2_2") (pintype "passive"))
      (node (ref "R48") (pin "2") (pinfunction "2_2") (pintype "passive"))
      (node (ref "R49") (pin "2") (pinfunction "2_2") (pintype "passive"))
      (node (ref "R50") (pin "2") (pinfunction "2_2") (pintype "passive"))
      (node (ref "R51") (pin "2") (pinfunction "2_2") (pintype "passive"))
      (node (ref "R52") (pin "2") (pinfunction "2_2") (pintype "passive"))
      (node (ref "R53") (pin "1") (pinfunction "1_1") (pintype "passive"))
      (node (ref "R54") (pin "1") (pinfunction "1_1") (pintype "passive"))
      (node (ref "R55") (pin "1") (pinfunction "1_1") (pintype "passive"))
      (node (ref "R56") (pin "1") (pinfunction "1_1") (pintype "passive"))
      (node (ref "R57") (pin "1") (pinfunction "1_1") (pintype "passive"))
      (node (ref "R58") (pin "1") (pinfunction "1_1") (pintype "passive"))
      (node (ref "R59") (pin "1") (pinfunction "1_1") (pintype "passive"))
      (node (ref "R60") (pin "1") (pinfunction "1_1") (pintype "passive"))
      (node (ref "RN2") (pin "1") (pinfunction "1_1") (pintype "passive"))
      (node (ref "RN5") (pin "1") (pinfunction "1_1") (pintype "passive"))
      (node (ref "SJ18") (pin "P$1") (pinfunction "1_P$1") (pintype "passive"))
      (node (ref "U$1") (pin "3V3") (pinfunction "3V3_3V3") (pintype "power_in"))
    )
    (net (code "2") (name "+5V") (class "Default")
      (node (ref "C3") (pin "1") (pinfunction "1_1") (pintype "passive"))
      (node (ref "C5") (pin "1") (pinfunction "1_1") (pintype "passive"))
      (node (ref "C8") (pin "1") (pinfunction "1_1") (pintype "passive"))
      (node (ref "C9") (pin "1") (pinfunction "1_1") (pintype "passive"))
      (node (ref "IC3") (pin "10") (pinfunction "SCL_10") (pintype "input"))
      (node (ref "IC3") (pin "16") (pinfunction "VCC_16") (pintype "power_in"))
      (node (ref "IC5") (pin "10") (pinfunction "SCL_10") (pintype "input"))
      (node (ref "IC5") (pin "16") (pinfunction "VCC_16") (pintype "power_in"))
      (node (ref "IC7") (pin "3") (pinfunction "VCC_3") (pintype "power_in"))
      (node (ref "JP10") (pin "2") (pinfunction "2_2") (pintype "passive"))
      (node (ref "JP11") (pin "3") (pinfunction "3_3") (pintype "passive"))
      (node (ref "JP11") (pin "4") (pinfunction "4_4") (pintype "passive"))
      (node (ref "JP12") (pin "3") (pinfunction "3_3") (pintype "passive"))
      (node (ref "JP12") (pin "4") (pinfunction "4_4") (pintype "passive"))
      (node (ref "JP13") (pin "6") (pinfunction "6_6") (pintype "passive"))
      (node (ref "JP14") (pin "6") (pinfunction "6_6") (pintype "passive"))
      (node (ref "JP15") (pin "6") (pinfunction "6_6") (pintype "passive"))
      (node (ref "JP16") (pin "3") (pinfunction "3_3") (pintype "passive"))
      (node (ref "JP16") (pin "4") (pinfunction "4_4") (pintype "passive"))
      (node (ref "JP7") (pin "3") (pinfunction "3_3") (pintype "passive"))
      (node (ref "JP7") (pin "4") (pinfunction "4_4") (pintype "passive"))
      (node (ref "JP8") (pin "3") (pinfunction "3_3") (pintype "passive"))
      (node (ref "R19") (pin "2") (pinfunction "2_2") (pintype "passive"))
      (node (ref "R20") (pin "2") (pinfunction "2_2") (pintype "passive"))
      (node (ref "R21") (pin "2") (pinfunction "2_2") (pintype "passive"))
      (node (ref "R22") (pin "1") (pinfunction "1_1") (pintype "passive"))
      (node (ref "R23") (pin "1") (pinfunction "1_1") (pintype "passive"))
      (node (ref "R24") (pin "1") (pinfunction "1_1") (pintype "passive"))
      (node (ref "R25") (pin "1") (pinfunction "1_1") (pintype "passive"))
      (node (ref "R26") (pin "1") (pinfunction "1_1") (pintype "passive"))
      (node (ref "R27") (pin "1") (pinfunction "1_1") (pintype "passive"))
      (node (ref "R62") (pin "1") (pinfunction "1_1") (pintype "passive"))
      (node (ref "R63") (pin "1") (pinfunction "1_1") (pintype "passive"))
      (node (ref "R64") (pin "1") (pinfunction "1_1") (pintype "passive"))
      (node (ref "R65") (pin "1") (pinfunction "1_1") (pintype "passive"))
      (node (ref "R66") (pin "1") (pinfunction "1_1") (pintype "passive"))
      (node (ref "R67") (pin "1") (pinfunction "1_1") (pintype "passive"))
      (node (ref "SJ1") (pin "P$2") (pinfunction "2_P$2") (pintype "passive"))
      (node (ref "SJ10") (pin "P$2") (pinfunction "2_P$2") (pintype "passive"))
      (node (ref "SJ4") (pin "P$2") (pinfunction "2_P$2") (pintype "passive"))
      (node (ref "SJ7") (pin "P$2") (pinfunction "2_P$2") (pintype "passive"))
      (node (ref "U$1") (pin "5V2") (pinfunction "5V2_5V2") (pintype "power_in"))
      (node (ref "U$6") (pin "3") (pinfunction "VDD_3") (pintype "power_in"))
      (node (ref "X1") (pin "1") (pinfunction "1_1") (pintype "passive"))
    )
    (net (code "3") (name "+12V") (class "Default")
      (node (ref "AP1509") (pin "1") (pinfunction "VIN_1") (pintype "bidirectional"))
      (node (ref "C10") (pin "1") (pinfunction "1_1") (pintype "passive"))
      (node (ref "C6") (pin "1") (pinfunction "1_1") (pintype "passive"))
      (node (ref "C7") (pin "1") (pinfunction "1_1") (pintype "passive"))
      (node (ref "IC10") (pin "5") (pinfunction "IN_5") (pintype "input"))
      (node (ref "IC6") (pin "4") (pinfunction "V+_4") (pintype "power_in"))
      (node (ref "IC9") (pin "4") (pinfunction "V+_4") (pintype "power_in"))
      (node (ref "J3") (pin "3") (pinfunction "3_3") (pintype "passive"))
      (node (ref "JP10") (pin "3") (pinfunction "3_3") (pintype "passive"))
      (node (ref "JP4") (pin "2") (pinfunction "2_2") (pintype "passive"))
      (node (ref "SJ11") (pin "P$2") (pinfunction "2_P$2") (pintype "passive"))
      (node (ref "SJ14") (pin "P$2") (pinfunction "2_P$2") (pintype "passive"))
      (node (ref "SJ2") (pin "P$2") (pinfunction "2_P$2") (pintype "passive"))
      (node (ref "SJ5") (pin "P$2") (pinfunction "2_P$2") (pintype "passive"))
      (node (ref "SJ8") (pin "P$2") (pinfunction "2_P$2") (pintype "passive"))
      (node (ref "U$2") (pin "6") (pinfunction "VDD_6") (pintype "power_in"))
      (node (ref "U$3") (pin "6") (pinfunction "VDD_6") (pintype "power_in"))
      (node (ref "U$4") (pin "6") (pinfunction "VDD_6") (pintype "power_in"))
      (node (ref "U$5") (pin "6") (pinfunction "VDD_6") (pintype "power_in"))
    )
    (net (code "4") (name "/AGND") (class "Default")
      (node (ref "U$1") (pin "AGND") (pinfunction "AGND_AGND") (pintype "power_in"))
    )
    (net (code "5") (name "/AVDD") (class "Default")
      (node (ref "U$1") (pin "AVDD") (pinfunction "AVDD_AVDD") (pintype "power_in"))
    )
    (net (code "6") (name "/CANH") (class "Default")
      (node (ref "IC7") (pin "7") (pinfunction "CANH_7") (pintype "bidirectional"))
      (node (ref "J1") (pin "1") (pinfunction "1_1") (pintype "passive"))
      (node (ref "J2") (pin "1") (pinfunction "1_1") (pintype "passive"))
      (node (ref "U$6") (pin "7") (pinfunction "CANH_7") (pintype "bidirectional"))
    )
    (net (code "7") (name "/CANL") (class "Default")
      (node (ref "IC7") (pin "6") (pinfunction "CANL_6") (pintype "bidirectional"))
      (node (ref "J1") (pin "2") (pinfunction "2_2") (pintype "passive"))
      (node (ref "J2") (pin "2") (pinfunction "2_2") (pintype "passive"))
      (node (ref "U$6") (pin "6") (pinfunction "CANL_6") (pintype "bidirectional"))
    )
    (net (code "8") (name "/GND4") (class "Default")
      (node (ref "U$1") (pin "GND4") (pinfunction "GND4_GND4") (pintype "power_in"))
    )
    (net (code "9") (name "/TIN5") (class "Default")
      (node (ref "IC6") (pin "3") (pinfunction "+IN_3") (pintype "input"))
      (node (ref "U$1") (pin "PA4") (pinfunction "PA4_PA4") (pintype "bidirectional"))
      (node (ref "U$5") (pin "4") (pinfunction "I_4") (pintype "input"))
    )
    (net (code "10") (name "/TIN6") (class "Default")
      (node (ref "IC6") (pin "5") (pinfunction "+IN_5") (pintype "input"))
      (node (ref "U$1") (pin "PC0") (pinfunction "PC0_PC0") (pintype "bidirectional"))
      (node (ref "U$4") (pin "2") (pinfunction "I_2") (pintype "input"))
    )
    (net (code "11") (name "/TIN8") (class "Default")
      (node (ref "IC6") (pin "12") (pinfunction "+IN_12") (pintype "input"))
      (node (ref "U$1") (pin "PA0") (pinfunction "PA0_PA0") (pintype "bidirectional"))
      (node (ref "U$5") (pin "2") (pinfunction "I_2") (pintype "input"))
    )
    (net (code "12") (name "/U5V") (class "Default")
      (node (ref "U$1") (pin "U5V") (pinfunction "U5V_U5V") (pintype "power_in"))
    )
    (net (code "13") (name "/VBAT") (class "Default")
      (node (ref "U$1") (pin "VBAT") (pinfunction "VBAT_VBAT") (pintype "power_in"))
    )
    (net (code "14") (name "/VDD") (class "Default")
      (node (ref "U$1") (pin "VDD") (pinfunction "VDD_VDD") (pintype "power_in"))
    )
    (net (code "15") (name "CANRX") (class "Default")
      (node (ref "IC7") (pin "4") (pinfunction "RXD_4") (pintype "output"))
      (node (ref "U$1") (pin "PB8") (pinfunction "PB8_PB8") (pintype "bidirectional"))
      (node (ref "U$6") (pin "4") (pinfunction "RXD_4") (pintype "bidirectional"))
    )
    (net (code "16") (name "CANTX") (class "Default")
      (node (ref "IC7") (pin "1") (pinfunction "TXD_1") (pintype "input"))
      (node (ref "U$1") (pin "PB9") (pinfunction "PB9_PB9") (pintype "bidirectional"))
      (node (ref "U$6") (pin "1") (pinfunction "TXD_1") (pintype "bidirectional"))
    )
    (net (code "17") (name "E_CS") (class "Default")
      (node (ref "JP9") (pin "4") (pinfunction "4_4") (pintype "passive"))
      (node (ref "R23") (pin "2") (pinfunction "2_2") (pintype "passive"))
      (node (ref "U$1") (pin "PC10") (pinfunction "PC10_PC10") (pintype "bidirectional"))
    )
    (net (code "18") (name "E_LAT") (class "Default")
      (node (ref "JP10") (pin "1") (pinfunction "1_1") (pintype "passive"))
      (node (ref "R22") (pin "2") (pinfunction "2_2") (pintype "passive"))
      (node (ref "U$1") (pin "PC11") (pinfunction "PC11_PC11") (pintype "bidirectional"))
    )
    (net (code "19") (name "GND") (class "Default")
      (node (ref "AP1509") (pin "4") (pinfunction "SD_4") (pintype "bidirectional"))
      (node (ref "AP1509") (pin "5") (pinfunction "GND1_5") (pintype "power_in"))
      (node (ref "AP1509") (pin "6") (pinfunction "GND2_6") (pintype "power_in"))
      (node (ref "AP1509") (pin "7") (pinfunction "GND3_7") (pintype "power_in"))
      (node (ref "AP1509") (pin "8") (pinfunction "GND4_8") (pintype "power_in"))
      (node (ref "C1") (pin "2") (pinfunction "2_2") (pintype "passive"))
      (node (ref "C10") (pin "2") (pinfunction "2_2") (pintype "passive"))
      (node (ref "C11") (pin "2") (pinfunction "2_2") (pintype "passive"))
      (node (ref "C2") (pin "-") (pinfunction "-_-") (pintype "passive"))
      (node (ref "C3") (pin "2") (pinfunction "2_2") (pintype "passive"))
      (node (ref "C4") (pin "2") (pinfunction "2_2") (pintype "passive"))
      (node (ref "C5") (pin "2") (pinfunction "2_2") (pintype "passive"))
      (node (ref "C6") (pin "2") (pinfunction "2_2") (pintype "passive"))
      (node (ref "C7") (pin "2") (pinfunction "2_2") (pintype "passive"))
      (node (ref "C8") (pin "2") (pinfunction "2_2") (pintype "passive"))
      (node (ref "C9") (pin "2") (pinfunction "2_2") (pintype "passive"))
      (node (ref "D1") (pin "A") (pinfunction "A_A") (pintype "passive"))
      (node (ref "IC1") (pin "6") (pinfunction "INH_6") (pintype "input"))
      (node (ref "IC1") (pin "8") (pinfunction "GND_8") (pintype "power_in"))
      (node (ref "IC10") (pin "2") (pinfunction "GNDSIG_2") (pintype "input"))
      (node (ref "IC10") (pin "3") (pinfunction "~{ON/OFF}_3") (pintype "input"))
      (node (ref "IC10") (pin "4") (pinfunction "GND_4") (pintype "power_in"))
      (node (ref "IC3") (pin "13") (pinfunction "G_13") (pintype "input"))
      (node (ref "IC3") (pin "8") (pinfunction "GND_8") (pintype "power_in"))
      (node (ref "IC4") (pin "6") (pinfunction "INH_6") (pintype "input"))
      (node (ref "IC4") (pin "8") (pinfunction "GND_8") (pintype "power_in"))
      (node (ref "IC5") (pin "13") (pinfunction "G_13") (pintype "input"))
      (node (ref "IC5") (pin "8") (pinfunction "GND_8") (pintype "power_in"))
      (node (ref "IC6") (pin "11") (pinfunction "V-_11") (pintype "power_in"))
      (node (ref "IC7") (pin "2") (pinfunction "GND_2") (pintype "power_in"))
      (node (ref "IC9") (pin "11") (pinfunction "V-_11") (pintype "power_in"))
      (node (ref "J1") (pin "3") (pinfunction "3_3") (pintype "passive"))
      (node (ref "J1") (pin "6") (pinfunction "6_6") (pintype "passive"))
      (node (ref "J1") (pin "7") (pinfunction "7_7") (pintype "passive"))
      (node (ref "J2") (pin "3") (pinfunction "3_3") (pintype "passive"))
      (node (ref "J2") (pin "6") (pinfunction "6_6") (pintype "passive"))
      (node (ref "J2") (pin "7") (pinfunction "7_7") (pintype "passive"))
      (node (ref "J3") (pin "1") (pinfunction "1_1") (pintype "passive"))
      (node (ref "JP10") (pin "4") (pinfunction "4_4") (pintype "passive"))
      (node (ref "JP11") (pin "5") (pinfunction "5_5") (pintype "passive"))
      (node (ref "JP11") (pin "6") (pinfunction "6_6") (pintype "passive"))
      (node (ref "JP12") (pin "5") (pinfunction "5_5") (pintype "passive"))
      (node (ref "JP12") (pin "6") (pinfunction "6_6") (pintype "passive"))
      (node (ref "JP13") (pin "5") (pinfunction "5_5") (pintype "passive"))
      (node (ref "JP14") (pin "5") (pinfunction "5_5") (pintype "passive"))
      (node (ref "JP15") (pin "5") (pinfunction "5_5") (pintype "passive"))
      (node (ref "JP16") (pin "5") (pinfunction "5_5") (pintype "passive"))
      (node (ref "JP16") (pin "6") (pinfunction "6_6") (pintype "passive"))
      (node (ref "JP7") (pin "5") (pinfunction "5_5") (pintype "passive"))
      (node (ref "JP7") (pin "6") (pinfunction "6_6") (pintype "passive"))
      (node (ref "JP8") (pin "4") (pinfunction "4_4") (pintype "passive"))
      (node (ref "Q1") (pin "2") (pinfunction "S_2") (pintype "passive"))
      (node (ref "Q10") (pin "2") (pinfunction "S_2") (pintype "passive"))
      (node (ref "Q11") (pin "2") (pinfunction "S_2") (pintype "passive"))
      (node (ref "Q12") (pin "2") (pinfunction "S_2") (pintype "passive"))
      (node (ref "Q13") (pin "2") (pinfunction "S_2") (pintype "passive"))
      (node (ref "Q14") (pin "2") (pinfunction "S_2") (pintype "passive"))
      (node (ref "Q15") (pin "2") (pinfunction "S_2") (pintype "passive"))
      (node (ref "Q16") (pin "2") (pinfunction "S_2") (pintype "passive"))
      (node (ref "Q2") (pin "2") (pinfunction "S_2") (pintype "passive"))
      (node (ref "Q3") (pin "2") (pinfunction "S_2") (pintype "passive"))
      (node (ref "Q4") (pin "2") (pinfunction "S_2") (pintype "passive"))
      (node (ref "Q5") (pin "2") (pinfunction "S_2") (pintype "passive"))
      (node (ref "Q6") (pin "2") (pinfunction "S_2") (pintype "passive"))
      (node (ref "Q7") (pin "2") (pinfunction "S_2") (pintype "passive"))
      (node (ref "Q8") (pin "2") (pinfunction "S_2") (pintype "passive"))
      (node (ref "Q9") (pin "2") (pinfunction "S_2") (pintype "passive"))
      (node (ref "R2") (pin "1") (pinfunction "1_1") (pintype "passive"))
      (node (ref "R61") (pin "2") (pinfunction "2_2") (pintype "passive"))
      (node (ref "SJ12") (pin "P$2") (pinfunction "2_P$2") (pintype "passive"))
      (node (ref "SJ3") (pin "2") (pinfunction "2_2") (pintype "passive"))
      (node (ref "SJ6") (pin "P$2") (pinfunction "2_P$2") (pintype "passive"))
      (node (ref "SJ9") (pin "2") (pinfunction "2_2") (pintype "passive"))
      (node (ref "U$1") (pin "GND3") (pinfunction "GND3_GND3") (pintype "power_in"))
      (node (ref "U$1") (pin "GND5") (pinfunction "GND5_GND5") (pintype "power_in"))
      (node (ref "U$1") (pin "GND6") (pinfunction "GND6_GND6") (pintype "power_in"))
      (node (ref "U$1") (pin "GND7") (pinfunction "GND7_GND7") (pintype "power_in"))
      (node (ref "U$1") (pin "GND8") (pinfunction "GND8_GND8") (pintype "power_in"))
      (node (ref "U$2") (pin "3") (pinfunction "VSS_3") (pintype "power_in"))
      (node (ref "U$3") (pin "3") (pinfunction "VSS_3") (pintype "power_in"))
      (node (ref "U$4") (pin "3") (pinfunction "VSS_3") (pintype "power_in"))
      (node (ref "U$5") (pin "3") (pinfunction "VSS_3") (pintype "power_in"))
      (node (ref "U$6") (pin "2") (pinfunction "VSS_2") (pintype "power_in"))
      (node (ref "X1") (pin "2") (pinfunction "2_2") (pintype "passive"))
    )
    (net (code "20") (name "I2CSCL") (class "Default")
      (node (ref "JP8") (pin "2") (pinfunction "2_2") (pintype "passive"))
      (node (ref "R63") (pin "2") (pinfunction "2_2") (pintype "passive"))
      (node (ref "U$1") (pin "PB6") (pinfunction "PB6_PB6") (pintype "bidirectional"))
    )
    (net (code "21") (name "I2CSDA") (class "Default")
      (node (ref "JP8") (pin "1") (pinfunction "1_1") (pintype "passive"))
      (node (ref "R62") (pin "2") (pinfunction "2_2") (pintype "passive"))
      (node (ref "U$1") (pin "PB7") (pinfunction "PB7_PB7") (pintype "bidirectional"))
    )
    (net (code "22") (name "ILAT") (class "Default")
      (node (ref "IC1") (pin "15") (pinfunction "SH/~{LD}_15") (pintype "input"))
      (node (ref "IC4") (pin "15") (pinfunction "SH/~{LD}_15") (pintype "input"))
      (node (ref "U$1") (pin "PA6") (pinfunction "PA6_PA6") (pintype "bidirectional"))
    )
    (net (code "23") (name "MISO") (class "Default")
      (node (ref "JP9") (pin "1") (pinfunction "1_1") (pintype "passive"))
      (node (ref "U$1") (pin "PB4") (pinfunction "PB4_PB4") (pintype "bidirectional"))
    )
    (net (code "24") (name "MISO2") (class "Default")
      (node (ref "IC4") (pin "13") (pinfunction "QH_13") (pintype "output"))
      (node (ref "SJ13") (pin "P$2") (pinfunction "2_P$2") (pintype "passive"))
      (node (ref "U$1") (pin "PC2") (pinfunction "PC2_PC2") (pintype "bidirectional"))
    )
    (net (code "25") (name "MOSI") (class "Default")
      (node (ref "IC5") (pin "14") (pinfunction "SER_14") (pintype "input"))
      (node (ref "R20") (pin "1") (pinfunction "1_1") (pintype "passive"))
      (node (ref "SJ15") (pin "1") (pinfunction "1_1") (pintype "passive"))
      (node (ref "SJ17") (pin "P$2") (pinfunction "2_P$2") (pintype "passive"))
      (node (ref "U$1") (pin "PB5") (pinfunction "PB5_PB5") (pintype "bidirectional"))
    )
    (net (code "26") (name "Net-(AP1509-VOUT)") (class "Default")
      (node (ref "AP1509") (pin "2") (pinfunction "VOUT_2") (pintype "bidirectional"))
      (node (ref "D1") (pin "C") (pinfunction "C_C") (pintype "passive"))
      (node (ref "IC10") (pin "7") (pinfunction "OUT_7") (pintype "passive"))
      (node (ref "L1") (pin "2") (pinfunction "2_2") (pintype "passive"))
    )
    (net (code "27") (name "Net-(D2-PadA)") (class "Default")
      (node (ref "D2") (pin "A") (pinfunction "A_A") (pintype "passive"))
      (node (ref "JP4") (pin "4") (pinfunction "4_4") (pintype "passive"))
    )
    (net (code "28") (name "Net-(D2-PadC)") (class "Default")
      (node (ref "D2") (pin "C") (pinfunction "C_C") (pintype "passive"))
      (node (ref "JP4") (pin "1") (pinfunction "1_1") (pintype "passive"))
    )
    (net (code "29") (name "Net-(IC1A-A)") (class "Default")
      (node (ref "IC1") (pin "2") (pinfunction "A_2") (pintype "input"))
      (node (ref "R36") (pin "1") (pinfunction "1_1") (pintype "passive"))
      (node (ref "RN4") (pin "9") (pinfunction "2_9") (pintype "passive"))
    )
    (net (code "30") (name "Net-(IC1A-B)") (class "Default")
      (node (ref "IC1") (pin "3") (pinfunction "B_3") (pintype "input"))
      (node (ref "R37") (pin "1") (pinfunction "1_1") (pintype "passive"))
      (node (ref "RN4") (pin "10") (pinfunction "2_10") (pintype "passive"))
    )
    (net (code "31") (name "Net-(IC1A-C)") (class "Default")
      (node (ref "IC1") (pin "4") (pinfunction "C_4") (pintype "input"))
      (node (ref "R38") (pin "1") (pinfunction "1_1") (pintype "passive"))
      (node (ref "RN4") (pin "11") (pinfunction "2_11") (pintype "passive"))
    )
    (net (code "32") (name "Net-(IC1A-D)") (class "Default")
      (node (ref "IC1") (pin "5") (pinfunction "D_5") (pintype "input"))
      (node (ref "R39") (pin "1") (pinfunction "1_1") (pintype "passive"))
      (node (ref "RN4") (pin "12") (pinfunction "2_12") (pintype "passive"))
    )
    (net (code "33") (name "Net-(IC1A-E)") (class "Default")
      (node (ref "IC1") (pin "10") (pinfunction "E_10") (pintype "input"))
      (node (ref "R41") (pin "1") (pinfunction "1_1") (pintype "passive"))
      (node (ref "RN4") (pin "13") (pinfunction "2_13") (pintype "passive"))
    )
    (net (code "34") (name "Net-(IC1A-F)") (class "Default")
      (node (ref "IC1") (pin "11") (pinfunction "F_11") (pintype "input"))
      (node (ref "R42") (pin "1") (pinfunction "1_1") (pintype "passive"))
      (node (ref "RN4") (pin "14") (pinfunction "2_14") (pintype "passive"))
    )
    (net (code "35") (name "Net-(IC1A-G)") (class "Default")
      (node (ref "IC1") (pin "12") (pinfunction "G_12") (pintype "input"))
      (node (ref "R43") (pin "1") (pinfunction "1_1") (pintype "passive"))
      (node (ref "RN4") (pin "15") (pinfunction "2_15") (pintype "passive"))
    )
    (net (code "36") (name "Net-(IC1A-H)") (class "Default")
      (node (ref "IC1") (pin "14") (pinfunction "H_14") (pintype "input"))
      (node (ref "R44") (pin "1") (pinfunction "1_1") (pintype "passive"))
      (node (ref "RN4") (pin "16") (pinfunction "2_16") (pintype "passive"))
    )
    (net (code "37") (name "Net-(IC2-CD+)") (class "Default")
      (node (ref "IC2") (pin "10") (pinfunction "CD+_10") (pintype "passive"))
      (node (ref "SJ4") (pin "P$1") (pinfunction "1_P$1") (pintype "passive"))
      (node (ref "SJ5") (pin "P$1") (pinfunction "1_P$1") (pintype "passive"))
      (node (ref "SJ6") (pin "P$1") (pinfunction "1_P$1") (pintype "passive"))
    )
    (net (code "38") (name "Net-(IC2-GND)") (class "Default")
      (node (ref "IC2") (pin "9") (pinfunction "GND_9") (pintype "power_in"))
      (node (ref "SJ1") (pin "P$1") (pinfunction "1_P$1") (pintype "passive"))
      (node (ref "SJ2") (pin "P$1") (pinfunction "1_P$1") (pintype "passive"))
      (node (ref "SJ3") (pin "1") (pinfunction "1_1") (pintype "passive"))
    )
    (net (code "39") (name "Net-(IC2-I1)") (class "Default")
      (node (ref "IC2") (pin "1") (pinfunction "I1_1") (pintype "input"))
      (node (ref "IC5") (pin "15") (pinfunction "QA_15") (pintype "tri_state"))
      (node (ref "R3") (pin "1") (pinfunction "1_1") (pintype "passive"))
    )
    (net (code "40") (name "Net-(IC2-I2)") (class "Default")
      (node (ref "IC2") (pin "2") (pinfunction "I2_2") (pintype "input"))
      (node (ref "IC5") (pin "1") (pinfunction "QB_1") (pintype "tri_state"))
      (node (ref "R4") (pin "1") (pinfunction "1_1") (pintype "passive"))
    )
    (net (code "41") (name "Net-(IC2-I3)") (class "Default")
      (node (ref "IC2") (pin "3") (pinfunction "I3_3") (pintype "input"))
      (node (ref "IC5") (pin "2") (pinfunction "QC_2") (pintype "tri_state"))
      (node (ref "R5") (pin "1") (pinfunction "1_1") (pintype "passive"))
    )
    (net (code "42") (name "Net-(IC2-I4)") (class "Default")
      (node (ref "IC2") (pin "4") (pinfunction "I4_4") (pintype "input"))
      (node (ref "IC5") (pin "3") (pinfunction "QD_3") (pintype "tri_state"))
      (node (ref "R6") (pin "1") (pinfunction "1_1") (pintype "passive"))
    )
    (net (code "43") (name "Net-(IC2-I5)") (class "Default")
      (node (ref "IC2") (pin "5") (pinfunction "I5_5") (pintype "input"))
      (node (ref "IC5") (pin "4") (pinfunction "QE_4") (pintype "tri_state"))
      (node (ref "R7") (pin "1") (pinfunction "1_1") (pintype "passive"))
    )
    (net (code "44") (name "Net-(IC2-I6)") (class "Default")
      (node (ref "IC2") (pin "6") (pinfunction "I6_6") (pintype "input"))
      (node (ref "IC5") (pin "5") (pinfunction "QF_5") (pintype "tri_state"))
      (node (ref "R8") (pin "1") (pinfunction "1_1") (pintype "passive"))
    )
    (net (code "45") (name "Net-(IC2-I7)") (class "Default")
      (node (ref "IC2") (pin "7") (pinfunction "I7_7") (pintype "input"))
      (node (ref "IC5") (pin "6") (pinfunction "QG_6") (pintype "tri_state"))
      (node (ref "R9") (pin "1") (pinfunction "1_1") (pintype "passive"))
    )
    (net (code "46") (name "Net-(IC2-I8)") (class "Default")
      (node (ref "IC2") (pin "8") (pinfunction "I8_8") (pintype "input"))
      (node (ref "IC5") (pin "7") (pinfunction "QH_7") (pintype "tri_state"))
      (node (ref "R10") (pin "1") (pinfunction "1_1") (pintype "passive"))
    )
    (net (code "47") (name "Net-(IC2-O1)") (class "Default")
      (node (ref "IC2") (pin "18") (pinfunction "O1_18") (pintype "open_collector"))
      (node (ref "JP1") (pin "1") (pinfunction "1_1") (pintype "passive"))
      (node (ref "Q1") (pin "3") (pinfunction "D_3") (pintype "passive"))
    )
    (net (code "48") (name "Net-(IC2-O2)") (class "Default")
      (node (ref "IC2") (pin "17") (pinfunction "O2_17") (pintype "open_collector"))
      (node (ref "JP1") (pin "2") (pinfunction "2_2") (pintype "passive"))
      (node (ref "Q2") (pin "3") (pinfunction "D_3") (pintype "passive"))
    )
    (net (code "49") (name "Net-(IC2-O3)") (class "Default")
      (node (ref "IC2") (pin "16") (pinfunction "O3_16") (pintype "open_collector"))
      (node (ref "JP1") (pin "3") (pinfunction "3_3") (pintype "passive"))
      (node (ref "Q3") (pin "3") (pinfunction "D_3") (pintype "passive"))
    )
    (net (code "50") (name "Net-(IC2-O4)") (class "Default")
      (node (ref "IC2") (pin "15") (pinfunction "O4_15") (pintype "open_collector"))
      (node (ref "JP1") (pin "4") (pinfunction "4_4") (pintype "passive"))
      (node (ref "Q4") (pin "3") (pinfunction "D_3") (pintype "passive"))
    )
    (net (code "51") (name "Net-(IC2-O5)") (class "Default")
      (node (ref "IC2") (pin "14") (pinfunction "O5_14") (pintype "open_collector"))
      (node (ref "JP1") (pin "5") (pinfunction "5_5") (pintype "passive"))
      (node (ref "Q5") (pin "3") (pinfunction "D_3") (pintype "passive"))
    )
    (net (code "52") (name "Net-(IC2-O6)") (class "Default")
      (node (ref "IC2") (pin "13") (pinfunction "O6_13") (pintype "open_collector"))
      (node (ref "JP1") (pin "6") (pinfunction "6_6") (pintype "passive"))
      (node (ref "Q6") (pin "3") (pinfunction "D_3") (pintype "passive"))
    )
    (net (code "53") (name "Net-(IC2-O7)") (class "Default")
      (node (ref "IC2") (pin "12") (pinfunction "O7_12") (pintype "open_collector"))
      (node (ref "JP1") (pin "7") (pinfunction "7_7") (pintype "passive"))
      (node (ref "Q7") (pin "3") (pinfunction "D_3") (pintype "passive"))
    )
    (net (code "54") (name "Net-(IC2-O8)") (class "Default")
      (node (ref "IC2") (pin "11") (pinfunction "O8_11") (pintype "open_collector"))
      (node (ref "JP1") (pin "8") (pinfunction "8_8") (pintype "passive"))
      (node (ref "Q8") (pin "3") (pinfunction "D_3") (pintype "passive"))
    )
    (net (code "55") (name "Net-(IC3A-QA)") (class "Default")
      (node (ref "IC3") (pin "15") (pinfunction "QA_15") (pintype "tri_state"))
      (node (ref "IC8") (pin "1") (pinfunction "I1_1") (pintype "input"))
      (node (ref "R11") (pin "1") (pinfunction "1_1") (pintype "passive"))
    )
    (net (code "56") (name "Net-(IC3A-QB)") (class "Default")
      (node (ref "IC3") (pin "1") (pinfunction "QB_1") (pintype "tri_state"))
      (node (ref "IC8") (pin "2") (pinfunction "I2_2") (pintype "input"))
      (node (ref "R12") (pin "1") (pinfunction "1_1") (pintype "passive"))
    )
    (net (code "57") (name "Net-(IC3A-QC)") (class "Default")
      (node (ref "IC3") (pin "2") (pinfunction "QC_2") (pintype "tri_state"))
      (node (ref "IC8") (pin "3") (pinfunction "I3_3") (pintype "input"))
      (node (ref "R13") (pin "1") (pinfunction "1_1") (pintype "passive"))
    )
    (net (code "58") (name "Net-(IC3A-QD)") (class "Default")
      (node (ref "IC3") (pin "3") (pinfunction "QD_3") (pintype "tri_state"))
      (node (ref "IC8") (pin "4") (pinfunction "I4_4") (pintype "input"))
      (node (ref "R14") (pin "1") (pinfunction "1_1") (pintype "passive"))
    )
    (net (code "59") (name "Net-(IC3A-QE)") (class "Default")
      (node (ref "IC3") (pin "4") (pinfunction "QE_4") (pintype "tri_state"))
      (node (ref "IC8") (pin "5") (pinfunction "I5_5") (pintype "input"))
      (node (ref "R15") (pin "1") (pinfunction "1_1") (pintype "passive"))
    )
    (net (code "60") (name "Net-(IC3A-QF)") (class "Default")
      (node (ref "IC3") (pin "5") (pinfunction "QF_5") (pintype "tri_state"))
      (node (ref "IC8") (pin "6") (pinfunction "I6_6") (pintype "input"))
      (node (ref "R16") (pin "1") (pinfunction "1_1") (pintype "passive"))
    )
    (net (code "61") (name "Net-(IC3A-QG)") (class "Default")
      (node (ref "IC3") (pin "6") (pinfunction "QG_6") (pintype "tri_state"))
      (node (ref "IC8") (pin "7") (pinfunction "I7_7") (pintype "input"))
      (node (ref "R17") (pin "1") (pinfunction "1_1") (pintype "passive"))
    )
    (net (code "62") (name "Net-(IC3A-QH)") (class "Default")
      (node (ref "IC3") (pin "7") (pinfunction "QH_7") (pintype "tri_state"))
      (node (ref "IC8") (pin "8") (pinfunction "I8_8") (pintype "input"))
      (node (ref "R18") (pin "1") (pinfunction "1_1") (pintype "passive"))
    )
    (net (code "63") (name "Net-(IC4A-A)") (class "Default")
      (node (ref "IC4") (pin "2") (pinfunction "A_2") (pintype "input"))
      (node (ref "R28") (pin "1") (pinfunction "1_1") (pintype "passive"))
      (node (ref "RN1") (pin "9") (pinfunction "2_9") (pintype "passive"))
    )
    (net (code "64") (name "Net-(IC4A-B)") (class "Default")
      (node (ref "IC4") (pin "3") (pinfunction "B_3") (pintype "input"))
      (node (ref "R29") (pin "1") (pinfunction "1_1") (pintype "passive"))
      (node (ref "RN1") (pin "10") (pinfunction "2_10") (pintype "passive"))
    )
    (net (code "65") (name "Net-(IC4A-C)") (class "Default")
      (node (ref "IC4") (pin "4") (pinfunction "C_4") (pintype "input"))
      (node (ref "R30") (pin "1") (pinfunction "1_1") (pintype "passive"))
      (node (ref "RN1") (pin "11") (pinfunction "2_11") (pintype "passive"))
    )
    (net (code "66") (name "Net-(IC4A-D)") (class "Default")
      (node (ref "IC4") (pin "5") (pinfunction "D_5") (pintype "input"))
      (node (ref "R31") (pin "1") (pinfunction "1_1") (pintype "passive"))
      (node (ref "RN1") (pin "12") (pinfunction "2_12") (pintype "passive"))
    )
    (net (code "67") (name "Net-(IC4A-E)") (class "Default")
      (node (ref "IC4") (pin "10") (pinfunction "E_10") (pintype "input"))
      (node (ref "R32") (pin "1") (pinfunction "1_1") (pintype "passive"))
      (node (ref "RN1") (pin "13") (pinfunction "2_13") (pintype "passive"))
    )
    (net (code "68") (name "Net-(IC4A-F)") (class "Default")
      (node (ref "IC4") (pin "11") (pinfunction "F_11") (pintype "input"))
      (node (ref "R33") (pin "1") (pinfunction "1_1") (pintype "passive"))
      (node (ref "RN1") (pin "14") (pinfunction "2_14") (pintype "passive"))
    )
    (net (code "69") (name "Net-(IC4A-G)") (class "Default")
      (node (ref "IC4") (pin "12") (pinfunction "G_12") (pintype "input"))
      (node (ref "R34") (pin "1") (pinfunction "1_1") (pintype "passive"))
      (node (ref "RN1") (pin "15") (pinfunction "2_15") (pintype "passive"))
    )
    (net (code "70") (name "Net-(IC4A-H)") (class "Default")
      (node (ref "IC4") (pin "14") (pinfunction "H_14") (pintype "input"))
      (node (ref "R35") (pin "1") (pinfunction "1_1") (pintype "passive"))
      (node (ref "RN1") (pin "16") (pinfunction "2_16") (pintype "passive"))
    )
    (net (code "71") (name "Net-(IC6A--IN)") (class "Default")
      (node (ref "IC6") (pin "13") (pinfunction "-IN_13") (pintype "input"))
      (node (ref "IC6") (pin "2") (pinfunction "-IN_2") (pintype "input"))
      (node (ref "IC6") (pin "6") (pinfunction "-IN_6") (pintype "input"))
      (node (ref "IC6") (pin "9") (pinfunction "-IN_9") (pintype "input"))
      (node (ref "IC9") (pin "13") (pinfunction "-IN_13") (pintype "input"))
      (node (ref "IC9") (pin "2") (pinfunction "-IN_2") (pintype "input"))
      (node (ref "IC9") (pin "6") (pinfunction "-IN_6") (pintype "input"))
      (node (ref "IC9") (pin "9") (pinfunction "-IN_9") (pintype "input"))
      (node (ref "R1") (pin "1") (pinfunction "1_1") (pintype "passive"))
      (node (ref "R2") (pin "2") (pinfunction "2_2") (pintype "passive"))
    )
    (net (code "72") (name "Net-(IC6A-OUT)") (class "Default")
      (node (ref "IC6") (pin "1") (pinfunction "OUT_1") (pintype "output"))
      (node (ref "JP15") (pin "3") (pinfunction "3_3") (pintype "passive"))
      (node (ref "JP5") (pin "3") (pinfunction "3_3") (pintype "passive"))
      (node (ref "U$5") (pin "5") (pinfunction "O_5") (pintype "output"))
    )
    (net (code "73") (name "Net-(IC6B-OUT)") (class "Default")
      (node (ref "IC6") (pin "7") (pinfunction "OUT_7") (pintype "output"))
      (node (ref "JP15") (pin "1") (pinfunction "1_1") (pintype "passive"))
      (node (ref "JP5") (pin "1") (pinfunction "1_1") (pintype "passive"))
      (node (ref "U$4") (pin "7") (pinfunction "O_7") (pintype "output"))
    )
    (net (code "74") (name "Net-(IC6C-OUT)") (class "Default")
      (node (ref "IC6") (pin "8") (pinfunction "OUT_8") (pintype "output"))
      (node (ref "JP15") (pin "2") (pinfunction "2_2") (pintype "passive"))
      (node (ref "JP5") (pin "2") (pinfunction "2_2") (pintype "passive"))
      (node (ref "U$4") (pin "5") (pinfunction "O_5") (pintype "output"))
    )
    (net (code "75") (name "Net-(IC6D-OUT)") (class "Default")
      (node (ref "IC6") (pin "14") (pinfunction "OUT_14") (pintype "output"))
      (node (ref "JP15") (pin "4") (pinfunction "4_4") (pintype "passive"))
      (node (ref "JP5") (pin "4") (pinfunction "4_4") (pintype "passive"))
      (node (ref "U$5") (pin "7") (pinfunction "O_7") (pintype "output"))
    )
    (net (code "76") (name "Net-(IC7-RS)") (class "Default")
      (node (ref "IC7") (pin "8") (pinfunction "RS_8") (pintype "input"))
      (node (ref "R61") (pin "1") (pinfunction "1_1") (pintype "passive"))
      (node (ref "U$6") (pin "8") (pinfunction "RS_8") (pintype "bidirectional"))
    )
    (net (code "77") (name "Net-(IC7-VREF)") (class "Default")
      (node (ref "IC7") (pin "5") (pinfunction "VREF_5") (pintype "output"))
      (node (ref "SJ18") (pin "P$2") (pinfunction "2_P$2") (pintype "passive"))
      (node (ref "U$6") (pin "5") (pinfunction "VREF_5") (pintype "bidirectional"))
    )
    (net (code "78") (name "Net-(IC8-CD+)") (class "Default")
      (node (ref "IC8") (pin "10") (pinfunction "CD+_10") (pintype "passive"))
      (node (ref "SJ10") (pin "P$1") (pinfunction "1_P$1") (pintype "passive"))
      (node (ref "SJ11") (pin "P$1") (pinfunction "1_P$1") (pintype "passive"))
      (node (ref "SJ12") (pin "P$1") (pinfunction "1_P$1") (pintype "passive"))
    )
    (net (code "79") (name "Net-(IC8-GND)") (class "Default")
      (node (ref "IC8") (pin "9") (pinfunction "GND_9") (pintype "power_in"))
      (node (ref "SJ7") (pin "P$1") (pinfunction "1_P$1") (pintype "passive"))
      (node (ref "SJ8") (pin "P$1") (pinfunction "1_P$1") (pintype "passive"))
      (node (ref "SJ9") (pin "1") (pinfunction "1_1") (pintype "passive"))
    )
    (net (code "80") (name "Net-(IC8-O1)") (class "Default")
      (node (ref "IC8") (pin "18") (pinfunction "O1_18") (pintype "open_collector"))
      (node (ref "JP6") (pin "1") (pinfunction "1_1") (pintype "passive"))
      (node (ref "Q9") (pin "3") (pinfunction "D_3") (pintype "passive"))
    )
    (net (code "81") (name "Net-(IC8-O2)") (class "Default")
      (node (ref "IC8") (pin "17") (pinfunction "O2_17") (pintype "open_collector"))
      (node (ref "JP6") (pin "2") (pinfunction "2_2") (pintype "passive"))
      (node (ref "Q10") (pin "3") (pinfunction "D_3") (pintype "passive"))
    )
    (net (code "82") (name "Net-(IC8-O3)") (class "Default")
      (node (ref "IC8") (pin "16") (pinfunction "O3_16") (pintype "open_collector"))
      (node (ref "JP6") (pin "3") (pinfunction "3_3") (pintype "passive"))
      (node (ref "Q11") (pin "3") (pinfunction "D_3") (pintype "passive"))
    )
    (net (code "83") (name "Net-(IC8-O4)") (class "Default")
      (node (ref "IC8") (pin "15") (pinfunction "O4_15") (pintype "open_collector"))
      (node (ref "JP6") (pin "4") (pinfunction "4_4") (pintype "passive"))
      (node (ref "Q12") (pin "3") (pinfunction "D_3") (pintype "passive"))
    )
    (net (code "84") (name "Net-(IC8-O5)") (class "Default")
      (node (ref "IC8") (pin "14") (pinfunction "O5_14") (pintype "open_collector"))
      (node (ref "JP6") (pin "5") (pinfunction "5_5") (pintype "passive"))
      (node (ref "Q13") (pin "3") (pinfunction "D_3") (pintype "passive"))
    )
    (net (code "85") (name "Net-(IC8-O6)") (class "Default")
      (node (ref "IC8") (pin "13") (pinfunction "O6_13") (pintype "open_collector"))
      (node (ref "JP6") (pin "6") (pinfunction "6_6") (pintype "passive"))
      (node (ref "Q14") (pin "3") (pinfunction "D_3") (pintype "passive"))
    )
    (net (code "86") (name "Net-(IC8-O7)") (class "Default")
      (node (ref "IC8") (pin "12") (pinfunction "O7_12") (pintype "open_collector"))
      (node (ref "JP6") (pin "7") (pinfunction "7_7") (pintype "passive"))
      (node (ref "Q15") (pin "3") (pinfunction "D_3") (pintype "passive"))
    )
    (net (code "87") (name "Net-(IC8-O8)") (class "Default")
      (node (ref "IC8") (pin "11") (pinfunction "O8_11") (pintype "open_collector"))
      (node (ref "JP6") (pin "8") (pinfunction "8_8") (pintype "passive"))
      (node (ref "Q16") (pin "3") (pinfunction "D_3") (pintype "passive"))
    )
    (net (code "88") (name "Net-(IC9A-OUT)") (class "Default")
      (node (ref "IC9") (pin "1") (pinfunction "OUT_1") (pintype "output"))
      (node (ref "JP15") (pin "9") (pinfunction "9_9") (pintype "passive"))
      (node (ref "JP5") (pin "7") (pinfunction "7_7") (pintype "passive"))
      (node (ref "U$3") (pin "5") (pinfunction "O_5") (pintype "output"))
    )
    (net (code "89") (name "Net-(IC9B-OUT)") (class "Default")
      (node (ref "IC9") (pin "7") (pinfunction "OUT_7") (pintype "output"))
      (node (ref "JP15") (pin "7") (pinfunction "7_7") (pintype "passive"))
      (node (ref "JP5") (pin "5") (pinfunction "5_5") (pintype "passive"))
      (node (ref "U$2") (pin "7") (pinfunction "O_7") (pintype "output"))
    )
    (net (code "90") (name "Net-(IC9C-OUT)") (class "Default")
      (node (ref "IC9") (pin "8") (pinfunction "OUT_8") (pintype "output"))
      (node (ref "JP15") (pin "8") (pinfunction "8_8") (pintype "passive"))
      (node (ref "JP5") (pin "6") (pinfunction "6_6") (pintype "passive"))
      (node (ref "U$2") (pin "5") (pinfunction "O_5") (pintype "output"))
    )
    (net (code "91") (name "Net-(IC9D-OUT)") (class "Default")
      (node (ref "IC9") (pin "14") (pinfunction "OUT_14") (pintype "output"))
      (node (ref "JP15") (pin "10") (pinfunction "10_10") (pintype "passive"))
      (node (ref "JP5") (pin "8") (pinfunction "8_8") (pintype "passive"))
      (node (ref "U$3") (pin "7") (pinfunction "O_7") (pintype "output"))
    )
    (net (code "92") (name "Net-(J1-Pad4)") (class "Default")
      (node (ref "J1") (pin "4") (pinfunction "4_4") (pintype "passive"))
      (node (ref "J2") (pin "4") (pinfunction "4_4") (pintype "passive"))
    )
    (net (code "93") (name "Net-(J1-Pad5)") (class "Default")
      (node (ref "J1") (pin "5") (pinfunction "5_5") (pintype "passive"))
      (node (ref "J2") (pin "5") (pinfunction "5_5") (pintype "passive"))
    )
    (net (code "94") (name "Net-(J1-Pad8)") (class "Default")
      (node (ref "J1") (pin "8") (pinfunction "8_8") (pintype "passive"))
      (node (ref "J2") (pin "8") (pinfunction "8_8") (pintype "passive"))
      (node (ref "R40") (pin "1") (pinfunction "1_1") (pintype "passive"))
    )
    (net (code "95") (name "Net-(JP4-Pad3)") (class "Default")
      (node (ref "JP4") (pin "3") (pinfunction "3_3") (pintype "passive"))
      (node (ref "R40") (pin "2") (pinfunction "2_2") (pintype "passive"))
    )
    (net (code "96") (name "Net-(JP13-Pad1)") (class "Default")
      (node (ref "JP13") (pin "1") (pinfunction "1_1") (pintype "passive"))
      (node (ref "JP3") (pin "1") (pinfunction "1_1") (pintype "passive"))
      (node (ref "R44") (pin "2") (pinfunction "2_2") (pintype "passive"))
      (node (ref "R53") (pin "2") (pinfunction "2_2") (pintype "passive"))
      (node (ref "RN4") (pin "1") (pinfunction "1_1") (pintype "passive"))
      (node (ref "RN5") (pin "9") (pinfunction "9_9") (pintype "passive"))
    )
    (net (code "97") (name "Net-(JP14-Pad1)") (class "Default")
      (node (ref "JP14") (pin "1") (pinfunction "1_1") (pintype "passive"))
      (node (ref "JP2") (pin "1") (pinfunction "1_1") (pintype "passive"))
      (node (ref "R35") (pin "2") (pinfunction "2_2") (pintype "passive"))
      (node (ref "R45") (pin "2") (pinfunction "2_2") (pintype "passive"))
      (node (ref "RN1") (pin "1") (pinfunction "1_1") (pintype "passive"))
      (node (ref "RN2") (pin "9") (pinfunction "9_9") (pintype "passive"))
    )
    (net (code "98") (name "Net-(Q1-G)") (class "Default")
      (node (ref "Q1") (pin "1") (pinfunction "G_1") (pintype "passive"))
      (node (ref "R3") (pin "2") (pinfunction "2_2") (pintype "passive"))
    )
    (net (code "99") (name "Net-(Q2-G)") (class "Default")
      (node (ref "Q2") (pin "1") (pinfunction "G_1") (pintype "passive"))
      (node (ref "R4") (pin "2") (pinfunction "2_2") (pintype "passive"))
    )
    (net (code "100") (name "Net-(Q3-G)") (class "Default")
      (node (ref "Q3") (pin "1") (pinfunction "G_1") (pintype "passive"))
      (node (ref "R5") (pin "2") (pinfunction "2_2") (pintype "passive"))
    )
    (net (code "101") (name "Net-(Q4-G)") (class "Default")
      (node (ref "Q4") (pin "1") (pinfunction "G_1") (pintype "passive"))
      (node (ref "R6") (pin "2") (pinfunction "2_2") (pintype "passive"))
    )
    (net (code "102") (name "Net-(Q5-G)") (class "Default")
      (node (ref "Q5") (pin "1") (pinfunction "G_1") (pintype "passive"))
      (node (ref "R7") (pin "2") (pinfunction "2_2") (pintype "passive"))
    )
    (net (code "103") (name "Net-(Q6-G)") (class "Default")
      (node (ref "Q6") (pin "1") (pinfunction "G_1") (pintype "passive"))
      (node (ref "R8") (pin "2") (pinfunction "2_2") (pintype "passive"))
    )
    (net (code "104") (name "Net-(Q7-G)") (class "Default")
      (node (ref "Q7") (pin "1") (pinfunction "G_1") (pintype "passive"))
      (node (ref "R9") (pin "2") (pinfunction "2_2") (pintype "passive"))
    )
    (net (code "105") (name "Net-(Q8-G)") (class "Default")
      (node (ref "Q8") (pin "1") (pinfunction "G_1") (pintype "passive"))
      (node (ref "R10") (pin "2") (pinfunction "2_2") (pintype "passive"))
    )
    (net (code "106") (name "Net-(Q9-G)") (class "Default")
      (node (ref "Q9") (pin "1") (pinfunction "G_1") (pintype "passive"))
      (node (ref "R11") (pin "2") (pinfunction "2_2") (pintype "passive"))
    )
    (net (code "107") (name "Net-(Q10-G)") (class "Default")
      (node (ref "Q10") (pin "1") (pinfunction "G_1") (pintype "passive"))
      (node (ref "R12") (pin "2") (pinfunction "2_2") (pintype "passive"))
    )
    (net (code "108") (name "Net-(Q11-G)") (class "Default")
      (node (ref "Q11") (pin "1") (pinfunction "G_1") (pintype "passive"))
      (node (ref "R13") (pin "2") (pinfunction "2_2") (pintype "passive"))
    )
    (net (code "109") (name "Net-(Q12-G)") (class "Default")
      (node (ref "Q12") (pin "1") (pinfunction "G_1") (pintype "passive"))
      (node (ref "R14") (pin "2") (pinfunction "2_2") (pintype "passive"))
    )
    (net (code "110") (name "Net-(Q13-G)") (class "Default")
      (node (ref "Q13") (pin "1") (pinfunction "G_1") (pintype "passive"))
      (node (ref "R15") (pin "2") (pinfunction "2_2") (pintype "passive"))
    )
    (net (code "111") (name "Net-(Q14-G)") (class "Default")
      (node (ref "Q14") (pin "1") (pinfunction "G_1") (pintype "passive"))
      (node (ref "R16") (pin "2") (pinfunction "2_2") (pintype "passive"))
    )
    (net (code "112") (name "Net-(Q15-G)") (class "Default")
      (node (ref "Q15") (pin "1") (pinfunction "G_1") (pintype "passive"))
      (node (ref "R17") (pin "2") (pinfunction "2_2") (pintype "passive"))
    )
    (net (code "113") (name "Net-(Q16-G)") (class "Default")
      (node (ref "Q16") (pin "1") (pinfunction "G_1") (pintype "passive"))
      (node (ref "R18") (pin "2") (pinfunction "2_2") (pintype "passive"))
    )
    (net (code "114") (name "Net-(RN1B-1)") (class "Default")
      (node (ref "JP14") (pin "2") (pinfunction "2_2") (pintype "passive"))
      (node (ref "JP2") (pin "2") (pinfunction "2_2") (pintype "passive"))
      (node (ref "R34") (pin "2") (pinfunction "2_2") (pintype "passive"))
      (node (ref "R46") (pin "1") (pinfunction "1_1") (pintype "passive"))
      (node (ref "RN1") (pin "2") (pinfunction "1_2") (pintype "passive"))
      (node (ref "RN2") (pin "8") (pinfunction "8_8") (pintype "passive"))
    )
    (net (code "115") (name "Net-(RN1C-1)") (class "Default")
      (node (ref "JP14") (pin "3") (pinfunction "3_3") (pintype "passive"))
      (node (ref "JP2") (pin "3") (pinfunction "3_3") (pintype "passive"))
      (node (ref "R33") (pin "2") (pinfunction "2_2") (pintype "passive"))
      (node (ref "R47") (pin "1") (pinfunction "1_1") (pintype "passive"))
      (node (ref "RN1") (pin "3") (pinfunction "1_3") (pintype "passive"))
      (node (ref "RN2") (pin "7") (pinfunction "7_7") (pintype "passive"))
    )
    (net (code "116") (name "Net-(RN1D-1)") (class "Default")
      (node (ref "JP14") (pin "4") (pinfunction "4_4") (pintype "passive"))
      (node (ref "JP2") (pin "4") (pinfunction "4_4") (pintype "passive"))
      (node (ref "R32") (pin "2") (pinfunction "2_2") (pintype "passive"))
      (node (ref "R48") (pin "1") (pinfunction "1_1") (pintype "passive"))
      (node (ref "RN1") (pin "4") (pinfunction "1_4") (pintype "passive"))
      (node (ref "RN2") (pin "6") (pinfunction "6_6") (pintype "passive"))
    )
    (net (code "117") (name "Net-(RN1E-1)") (class "Default")
      (node (ref "JP14") (pin "7") (pinfunction "7_7") (pintype "passive"))
      (node (ref "JP2") (pin "5") (pinfunction "5_5") (pintype "passive"))
      (node (ref "R31") (pin "2") (pinfunction "2_2") (pintype "passive"))
      (node (ref "R49") (pin "1") (pinfunction "1_1") (pintype "passive"))
      (node (ref "RN1") (pin "5") (pinfunction "1_5") (pintype "passive"))
      (node (ref "RN2") (pin "5") (pinfunction "5_5") (pintype "passive"))
    )
    (net (code "118") (name "Net-(RN1F-1)") (class "Default")
      (node (ref "JP14") (pin "8") (pinfunction "8_8") (pintype "passive"))
      (node (ref "JP2") (pin "6") (pinfunction "6_6") (pintype "passive"))
      (node (ref "R30") (pin "2") (pinfunction "2_2") (pintype "passive"))
      (node (ref "R50") (pin "1") (pinfunction "1_1") (pintype "passive"))
      (node (ref "RN1") (pin "6") (pinfunction "1_6") (pintype "passive"))
      (node (ref "RN2") (pin "4") (pinfunction "4_4") (pintype "passive"))
    )
    (net (code "119") (name "Net-(RN1G-1)") (class "Default")
      (node (ref "JP14") (pin "9") (pinfunction "9_9") (pintype "passive"))
      (node (ref "JP2") (pin "7") (pinfunction "7_7") (pintype "passive"))
      (node (ref "R29") (pin "2") (pinfunction "2_2") (pintype "passive"))
      (node (ref "R51") (pin "1") (pinfunction "1_1") (pintype "passive"))
      (node (ref "RN1") (pin "7") (pinfunction "1_7") (pintype "passive"))
      (node (ref "RN2") (pin "3") (pinfunction "3_3") (pintype "passive"))
    )
    (net (code "120") (name "Net-(RN1H-1)") (class "Default")
      (node (ref "JP14") (pin "10") (pinfunction "10_10") (pintype "passive"))
      (node (ref "JP2") (pin "8") (pinfunction "8_8") (pintype "passive"))
      (node (ref "R28") (pin "2") (pinfunction "2_2") (pintype "passive"))
      (node (ref "R52") (pin "1") (pinfunction "1_1") (pintype "passive"))
      (node (ref "RN1") (pin "8") (pinfunction "1_8") (pintype "passive"))
      (node (ref "RN2") (pin "2") (pinfunction "2_2") (pintype "passive"))
    )
    (net (code "121") (name "Net-(RN4B-1)") (class "Default")
      (node (ref "JP13") (pin "2") (pinfunction "2_2") (pintype "passive"))
      (node (ref "JP3") (pin "2") (pinfunction "2_2") (pintype "passive"))
      (node (ref "R43") (pin "2") (pinfunction "2_2") (pintype "passive"))
      (node (ref "R54") (pin "2") (pinfunction "2_2") (pintype "passive"))
      (node (ref "RN4") (pin "2") (pinfunction "1_2") (pintype "passive"))
      (node (ref "RN5") (pin "8") (pinfunction "8_8") (pintype "passive"))
    )
    (net (code "122") (name "Net-(RN4C-1)") (class "Default")
      (node (ref "JP13") (pin "3") (pinfunction "3_3") (pintype "passive"))
      (node (ref "JP3") (pin "3") (pinfunction "3_3") (pintype "passive"))
      (node (ref "R42") (pin "2") (pinfunction "2_2") (pintype "passive"))
      (node (ref "R55") (pin "2") (pinfunction "2_2") (pintype "passive"))
      (node (ref "RN4") (pin "3") (pinfunction "1_3") (pintype "passive"))
      (node (ref "RN5") (pin "7") (pinfunction "7_7") (pintype "passive"))
    )
    (net (code "123") (name "Net-(RN4D-1)") (class "Default")
      (node (ref "JP13") (pin "4") (pinfunction "4_4") (pintype "passive"))
      (node (ref "JP3") (pin "4") (pinfunction "4_4") (pintype "passive"))
      (node (ref "R41") (pin "2") (pinfunction "2_2") (pintype "passive"))
      (node (ref "R56") (pin "2") (pinfunction "2_2") (pintype "passive"))
      (node (ref "RN4") (pin "4") (pinfunction "1_4") (pintype "passive"))
      (node (ref "RN5") (pin "6") (pinfunction "6_6") (pintype "passive"))
    )
    (net (code "124") (name "Net-(RN4E-1)") (class "Default")
      (node (ref "JP13") (pin "7") (pinfunction "7_7") (pintype "passive"))
      (node (ref "JP3") (pin "5") (pinfunction "5_5") (pintype "passive"))
      (node (ref "R39") (pin "2") (pinfunction "2_2") (pintype "passive"))
      (node (ref "R57") (pin "2") (pinfunction "2_2") (pintype "passive"))
      (node (ref "RN4") (pin "5") (pinfunction "1_5") (pintype "passive"))
      (node (ref "RN5") (pin "5") (pinfunction "5_5") (pintype "passive"))
    )
    (net (code "125") (name "Net-(RN4F-1)") (class "Default")
      (node (ref "JP13") (pin "8") (pinfunction "8_8") (pintype "passive"))
      (node (ref "JP3") (pin "6") (pinfunction "6_6") (pintype "passive"))
      (node (ref "R38") (pin "2") (pinfunction "2_2") (pintype "passive"))
      (node (ref "R58") (pin "2") (pinfunction "2_2") (pintype "passive"))
      (node (ref "RN4") (pin "6") (pinfunction "1_6") (pintype "passive"))
      (node (ref "RN5") (pin "4") (pinfunction "4_4") (pintype "passive"))
    )
    (net (code "126") (name "Net-(RN4G-1)") (class "Default")
      (node (ref "JP13") (pin "9") (pinfunction "9_9") (pintype "passive"))
      (node (ref "JP3") (pin "7") (pinfunction "7_7") (pintype "passive"))
      (node (ref "R37") (pin "2") (pinfunction "2_2") (pintype "passive"))
      (node (ref "R59") (pin "2") (pinfunction "2_2") (pintype "passive"))
      (node (ref "RN4") (pin "7") (pinfunction "1_7") (pintype "passive"))
      (node (ref "RN5") (pin "3") (pinfunction "3_3") (pintype "passive"))
    )
    (net (code "127") (name "Net-(RN4H-1)") (class "Default")
      (node (ref "JP13") (pin "10") (pinfunction "10_10") (pintype "passive"))
      (node (ref "JP3") (pin "8") (pinfunction "8_8") (pintype "passive"))
      (node (ref "R36") (pin "2") (pinfunction "2_2") (pintype "passive"))
      (node (ref "R60") (pin "2") (pinfunction "2_2") (pintype "passive"))
      (node (ref "RN4") (pin "8") (pinfunction "1_8") (pintype "passive"))
      (node (ref "RN5") (pin "2") (pinfunction "2_2") (pintype "passive"))
    )
    (net (code "128") (name "Net-(SJ13-1)") (class "Default")
      (node (ref "SJ13") (pin "P$1") (pinfunction "1_P$1") (pintype "passive"))
      (node (ref "U$1") (pin "PB14") (pinfunction "PB14_PB14") (pintype "bidirectional"))
    )
    (net (code "129") (name "Net-(SJ14-1)") (class "Default")
      (node (ref "SJ14") (pin "P$1") (pinfunction "1_P$1") (pintype "passive"))
      (node (ref "U$1") (pin "VIN2") (pinfunction "VIN2_VIN2") (pintype "power_in"))
    )
    (net (code "130") (name "Net-(SJ16-2)") (class "Default")
      (node (ref "JP9") (pin "2") (pinfunction "2_2") (pintype "passive"))
      (node (ref "SJ15") (pin "2") (pinfunction "2_2") (pintype "passive"))
      (node (ref "SJ16") (pin "P$2") (pinfunction "2_P$2") (pintype "passive"))
    )
    (net (code "131") (name "OLAT") (class "Default")
      (node (ref "IC3") (pin "12") (pinfunction "RCK_12") (pintype "input"))
      (node (ref "IC5") (pin "12") (pinfunction "RCK_12") (pintype "input"))
      (node (ref "R21") (pin "1") (pinfunction "1_1") (pintype "passive"))
      (node (ref "U$1") (pin "PA8") (pinfunction "PA8_PA8") (pintype "bidirectional"))
    )
    (net (code "132") (name "SCK") (class "Default")
      (node (ref "IC3") (pin "11") (pinfunction "SCK_11") (pintype "input"))
      (node (ref "IC5") (pin "11") (pinfunction "SCK_11") (pintype "input"))
      (node (ref "JP9") (pin "3") (pinfunction "3_3") (pintype "passive"))
      (node (ref "R19") (pin "1") (pinfunction "1_1") (pintype "passive"))
      (node (ref "U$1") (pin "PB3") (pinfunction "PB3_PB3") (pintype "bidirectional"))
    )
    (net (code "133") (name "SCK2") (class "Default")
      (node (ref "IC1") (pin "7") (pinfunction "CLK_7") (pintype "input"))
      (node (ref "IC4") (pin "7") (pinfunction "CLK_7") (pintype "input"))
      (node (ref "U$1") (pin "PB10") (pinfunction "PB10_PB10") (pintype "bidirectional"))
    )
    (net (code "134") (name "SLNK1") (class "Default")
      (node (ref "IC3") (pin "14") (pinfunction "SER_14") (pintype "input"))
      (node (ref "IC5") (pin "9") (pinfunction "QH*_9") (pintype "tri_state"))
      (node (ref "SJ17") (pin "P$1") (pinfunction "1_P$1") (pintype "passive"))
    )
    (net (code "135") (name "SLNK2") (class "Default")
      (node (ref "IC3") (pin "9") (pinfunction "QH*_9") (pintype "tri_state"))
      (node (ref "SJ16") (pin "P$1") (pinfunction "1_P$1") (pintype "passive"))
    )
    (net (code "136") (name "SLNK3") (class "Default")
      (node (ref "IC1") (pin "13") (pinfunction "QH_13") (pintype "output"))
      (node (ref "IC4") (pin "1") (pinfunction "SER_1") (pintype "input"))
    )
    (net (code "137") (name "SRV1") (class "Default")
      (node (ref "JP7") (pin "2") (pinfunction "2_2") (pintype "passive"))
      (node (ref "R25") (pin "2") (pinfunction "2_2") (pintype "passive"))
      (node (ref "U$1") (pin "PC9") (pinfunction "PC9_PC9") (pintype "bidirectional"))
    )
    (net (code "138") (name "SRV2") (class "Default")
      (node (ref "JP7") (pin "1") (pinfunction "1_1") (pintype "passive"))
      (node (ref "R24") (pin "2") (pinfunction "2_2") (pintype "passive"))
      (node (ref "U$1") (pin "PC7") (pinfunction "PC7_PC7") (pintype "bidirectional"))
    )
    (net (code "139") (name "SRV3") (class "Default")
      (node (ref "JP11") (pin "2") (pinfunction "2_2") (pintype "passive"))
      (node (ref "R26") (pin "2") (pinfunction "2_2") (pintype "passive"))
      (node (ref "U$1") (pin "PC8") (pinfunction "PC8_PC8") (pintype "bidirectional"))
    )
    (net (code "140") (name "SRV4") (class "Default")
      (node (ref "JP11") (pin "1") (pinfunction "1_1") (pintype "passive"))
      (node (ref "R27") (pin "2") (pinfunction "2_2") (pintype "passive"))
      (node (ref "U$1") (pin "PC6") (pinfunction "PC6_PC6") (pintype "bidirectional"))
    )
    (net (code "141") (name "SRV5") (class "Default")
      (node (ref "JP12") (pin "2") (pinfunction "2_2") (pintype "passive"))
      (node (ref "R64") (pin "2") (pinfunction "2_2") (pintype "passive"))
      (node (ref "U$1") (pin "PF1-PH1") (pinfunction "PF1-PH1_PF1-PH1") (pintype "bidirectional"))
    )
    (net (code "142") (name "SRV6") (class "Default")
      (node (ref "JP12") (pin "1") (pinfunction "1_1") (pintype "passive"))
      (node (ref "R65") (pin "2") (pinfunction "2_2") (pintype "passive"))
      (node (ref "U$1") (pin "PA15") (pinfunction "PA15_PA15") (pintype "bidirectional"))
    )
    (net (code "143") (name "SRV7") (class "Default")
      (node (ref "JP16") (pin "2") (pinfunction "2_2") (pintype "passive"))
      (node (ref "R66") (pin "2") (pinfunction "2_2") (pintype "passive"))
      (node (ref "U$1") (pin "PC12") (pinfunction "PC12_PC12") (pintype "bidirectional"))
    )
    (net (code "144") (name "SRV8") (class "Default")
      (node (ref "JP16") (pin "1") (pinfunction "1_1") (pintype "passive"))
      (node (ref "R67") (pin "2") (pinfunction "2_2") (pintype "passive"))
      (node (ref "U$1") (pin "PD2") (pinfunction "PD2_PD2") (pintype "bidirectional"))
    )
    (net (code "145") (name "TIN1") (class "Default")
      (node (ref "IC9") (pin "3") (pinfunction "+IN_3") (pintype "input"))
      (node (ref "U$1") (pin "PB2") (pinfunction "PB2_PB2") (pintype "bidirectional"))
      (node (ref "U$3") (pin "4") (pinfunction "I_4") (pintype "input"))
    )
    (net (code "146") (name "TIN2") (class "Default")
      (node (ref "IC9") (pin "5") (pinfunction "+IN_5") (pintype "input"))
      (node (ref "U$1") (pin "PB1") (pinfunction "PB1_PB1") (pintype "bidirectional"))
      (node (ref "U$2") (pin "2") (pinfunction "I_2") (pintype "input"))
    )
    (net (code "147") (name "TIN3") (class "Default")
      (node (ref "IC9") (pin "10") (pinfunction "+IN_10") (pintype "input"))
      (node (ref "U$1") (pin "PB15") (pinfunction "PB15_PB15") (pintype "bidirectional"))
      (node (ref "U$2") (pin "4") (pinfunction "I_4") (pintype "input"))
    )
    (net (code "148") (name "TIN4") (class "Default")
      (node (ref "IC9") (pin "12") (pinfunction "+IN_12") (pintype "input"))
      (node (ref "U$1") (pin "PB12") (pinfunction "PB12_PB12") (pintype "bidirectional"))
      (node (ref "U$3") (pin "2") (pinfunction "I_2") (pintype "input"))
    )
    (net (code "149") (name "TIN7") (class "Default")
      (node (ref "IC6") (pin "10") (pinfunction "+IN_10") (pintype "input"))
      (node (ref "U$1") (pin "PC3") (pinfunction "PC3_PC3") (pintype "bidirectional"))
      (node (ref "U$4") (pin "4") (pinfunction "I_4") (pintype "input"))
    )
    (net (code "150") (name "V+") (class "Default")
      (node (ref "AP1509") (pin "3") (pinfunction "FB_3") (pintype "bidirectional"))
      (node (ref "C1") (pin "1") (pinfunction "1_1") (pintype "passive"))
      (node (ref "C2") (pin "+") (pinfunction "+_+") (pintype "passive"))
      (node (ref "IC10") (pin "1") (pinfunction "FB_1") (pintype "input"))
      (node (ref "L1") (pin "1") (pinfunction "1_1") (pintype "passive"))
      (node (ref "U$1") (pin "E5V") (pinfunction "E5V_E5V") (pintype "power_in"))
    )
    (net (code "151") (name "unconnected-(H1-MOUNT-PadB3,3)") (class "Default")
      (node (ref "H1") (pin "B3,3") (pinfunction "MOUNT_B3,3") (pintype "passive"))
    )
    (net (code "152") (name "unconnected-(H2-MOUNT-PadB3,3)") (class "Default")
      (node (ref "H2") (pin "B3,3") (pinfunction "MOUNT_B3,3") (pintype "passive"))
    )
    (net (code "153") (name "unconnected-(H3-MOUNT-PadB3,3)") (class "Default")
      (node (ref "H3") (pin "B3,3") (pinfunction "MOUNT_B3,3") (pintype "passive"))
    )
    (net (code "154") (name "unconnected-(H4-MOUNT-PadB3,3)") (class "Default")
      (node (ref "H4") (pin "B3,3") (pinfunction "MOUNT_B3,3") (pintype "passive"))
    )
    (net (code "155") (name "unconnected-(J3-Pad2)") (class "Default")
      (node (ref "J3") (pin "2") (pinfunction "2_2") (pintype "passive"))
    )
    (net (code "156") (name "unconnected-(U$1-PadBOOT0)") (class "Default")
      (node (ref "U$1") (pin "BOOT0") (pinfunction "BOOT0_BOOT0") (pintype "bidirectional"))
    )
    (net (code "157") (name "unconnected-(U$1-PadIOREF2)") (class "Default")
      (node (ref "U$1") (pin "IOREF2") (pinfunction "IOREF2_IOREF2") (pintype "input"))
    )
    (net (code "158") (name "unconnected-(U$1-PadNC1-PF7)") (class "Default")
      (node (ref "U$1") (pin "NC1-PF7") (pinfunction "NC1-PF7_NC1-PF7") (pintype "bidirectional"))
    )
    (net (code "159") (name "unconnected-(U$1-PadNC2-PF6)") (class "Default")
      (node (ref "U$1") (pin "NC2-PF6") (pinfunction "NC2-PF6_NC2-PF6") (pintype "bidirectional"))
    )
    (net (code "160") (name "unconnected-(U$1-PadNC3)") (class "Default")
      (node (ref "U$1") (pin "NC3") (pinfunction "NC3_NC3") (pintype "no_connect"))
    )
    (net (code "161") (name "unconnected-(U$1-PadNC4)") (class "Default")
      (node (ref "U$1") (pin "NC4") (pinfunction "NC4_NC4") (pintype "no_connect"))
    )
    (net (code "162") (name "unconnected-(U$1-PadNC5-PD8)") (class "Default")
      (node (ref "U$1") (pin "NC5-PD8") (pinfunction "NC5-PD8_NC5-PD8") (pintype "bidirectional"))
    )
    (net (code "163") (name "unconnected-(U$1-PadNC6-PB11)") (class "Default")
      (node (ref "U$1") (pin "NC6-PB11") (pinfunction "NC6-PB11_NC6-PB11") (pintype "no_connect"))
    )
    (net (code "164") (name "unconnected-(U$1-PadNC7-PF5)") (class "Default")
      (node (ref "U$1") (pin "NC7-PF5") (pinfunction "NC7-PF5_NC7-PF5") (pintype "bidirectional"))
    )
    (net (code "165") (name "unconnected-(U$1-PadNC8-PF4)") (class "Default")
      (node (ref "U$1") (pin "NC8-PF4") (pinfunction "NC8-PF4_NC8-PF4") (pintype "bidirectional"))
    )
    (net (code "166") (name "unconnected-(U$1-PadNRESET)") (class "Default")
      (node (ref "U$1") (pin "NRESET") (pinfunction "NRESET_NRESET") (pintype "input"))
    )
    (net (code "167") (name "unconnected-(U$1-PadPA1)") (class "Default")
      (node (ref "U$1") (pin "PA1") (pinfunction "PA1_PA1") (pintype "bidirectional"))
    )
    (net (code "168") (name "unconnected-(U$1-PadPA2)") (class "Default")
      (node (ref "U$1") (pin "PA2") (pinfunction "PA2_PA2") (pintype "bidirectional"))
    )
    (net (code "169") (name "unconnected-(U$1-PadPA3)") (class "Default")
      (node (ref "U$1") (pin "PA3") (pinfunction "PA3_PA3") (pintype "bidirectional"))
    )
    (net (code "170") (name "unconnected-(U$1-PadPA5)") (class "Default")
      (node (ref "U$1") (pin "PA5") (pinfunction "PA5_PA5") (pintype "bidirectional"))
    )
    (net (code "171") (name "unconnected-(U$1-PadPA7)") (class "Default")
      (node (ref "U$1") (pin "PA7") (pinfunction "PA7_PA7") (pintype "bidirectional"))
    )
    (net (code "172") (name "unconnected-(U$1-PadPA9)") (class "Default")
      (node (ref "U$1") (pin "PA9") (pinfunction "PA9_PA9") (pintype "bidirectional"))
    )
    (net (code "173") (name "unconnected-(U$1-PadPA10)") (class "Default")
      (node (ref "U$1") (pin "PA10") (pinfunction "PA10_PA10") (pintype "bidirectional"))
    )
    (net (code "174") (name "unconnected-(U$1-PadPA11)") (class "Default")
      (node (ref "U$1") (pin "PA11") (pinfunction "PA11_PA11") (pintype "bidirectional"))
    )
    (net (code "175") (name "unconnected-(U$1-PadPA12)") (class "Default")
      (node (ref "U$1") (pin "PA12") (pinfunction "PA12_PA12") (pintype "bidirectional"))
    )
    (net (code "176") (name "unconnected-(U$1-PadPA13)") (class "Default")
      (node (ref "U$1") (pin "PA13") (pinfunction "PA13_PA13") (pintype "bidirectional"))
    )
    (net (code "177") (name "unconnected-(U$1-PadPA14)") (class "Default")
      (node (ref "U$1") (pin "PA14") (pinfunction "PA14_PA14") (pintype "bidirectional"))
    )
    (net (code "178") (name "unconnected-(U$1-PadPB0)") (class "Default")
      (node (ref "U$1") (pin "PB0") (pinfunction "PB0_PB0") (pintype "bidirectional"))
    )
    (net (code "179") (name "unconnected-(U$1-PadPB13)") (class "Default")
      (node (ref "U$1") (pin "PB13") (pinfunction "PB13_PB13") (pintype "bidirectional"))
    )
    (net (code "180") (name "unconnected-(U$1-PadPC1)") (class "Default")
      (node (ref "U$1") (pin "PC1") (pinfunction "PC1_PC1") (pintype "bidirectional"))
    )
    (net (code "181") (name "unconnected-(U$1-PadPC4)") (class "Default")
      (node (ref "U$1") (pin "PC4") (pinfunction "PC4_PC4") (pintype "bidirectional"))
    )
    (net (code "182") (name "unconnected-(U$1-PadPC5)") (class "Default")
      (node (ref "U$1") (pin "PC5") (pinfunction "PC5_PC5") (pintype "bidirectional"))
    )
    (net (code "183") (name "unconnected-(U$1-PadPC13)") (class "Default")
      (node (ref "U$1") (pin "PC13") (pinfunction "PC13_PC13") (pintype "bidirectional"))
    )
    (net (code "184") (name "unconnected-(U$1-PadPC14)") (class "Default")
      (node (ref "U$1") (pin "PC14") (pinfunction "PC14_PC14") (pintype "bidirectional"))
    )
    (net (code "185") (name "unconnected-(U$1-PadPC15)") (class "Default")
      (node (ref "U$1") (pin "PC15") (pinfunction "PC15_PC15") (pintype "bidirectional"))
    )
    (net (code "186") (name "unconnected-(U$1-PadPF0-PH0)") (class "Default")
      (node (ref "U$1") (pin "PF0-PH0") (pinfunction "PF0-PH0_PF0-PH0") (pintype "bidirectional"))
    )
  )
)
